# STM32_V2.net
KiCad netlist of a schematic drawn in EasyEDA Pro
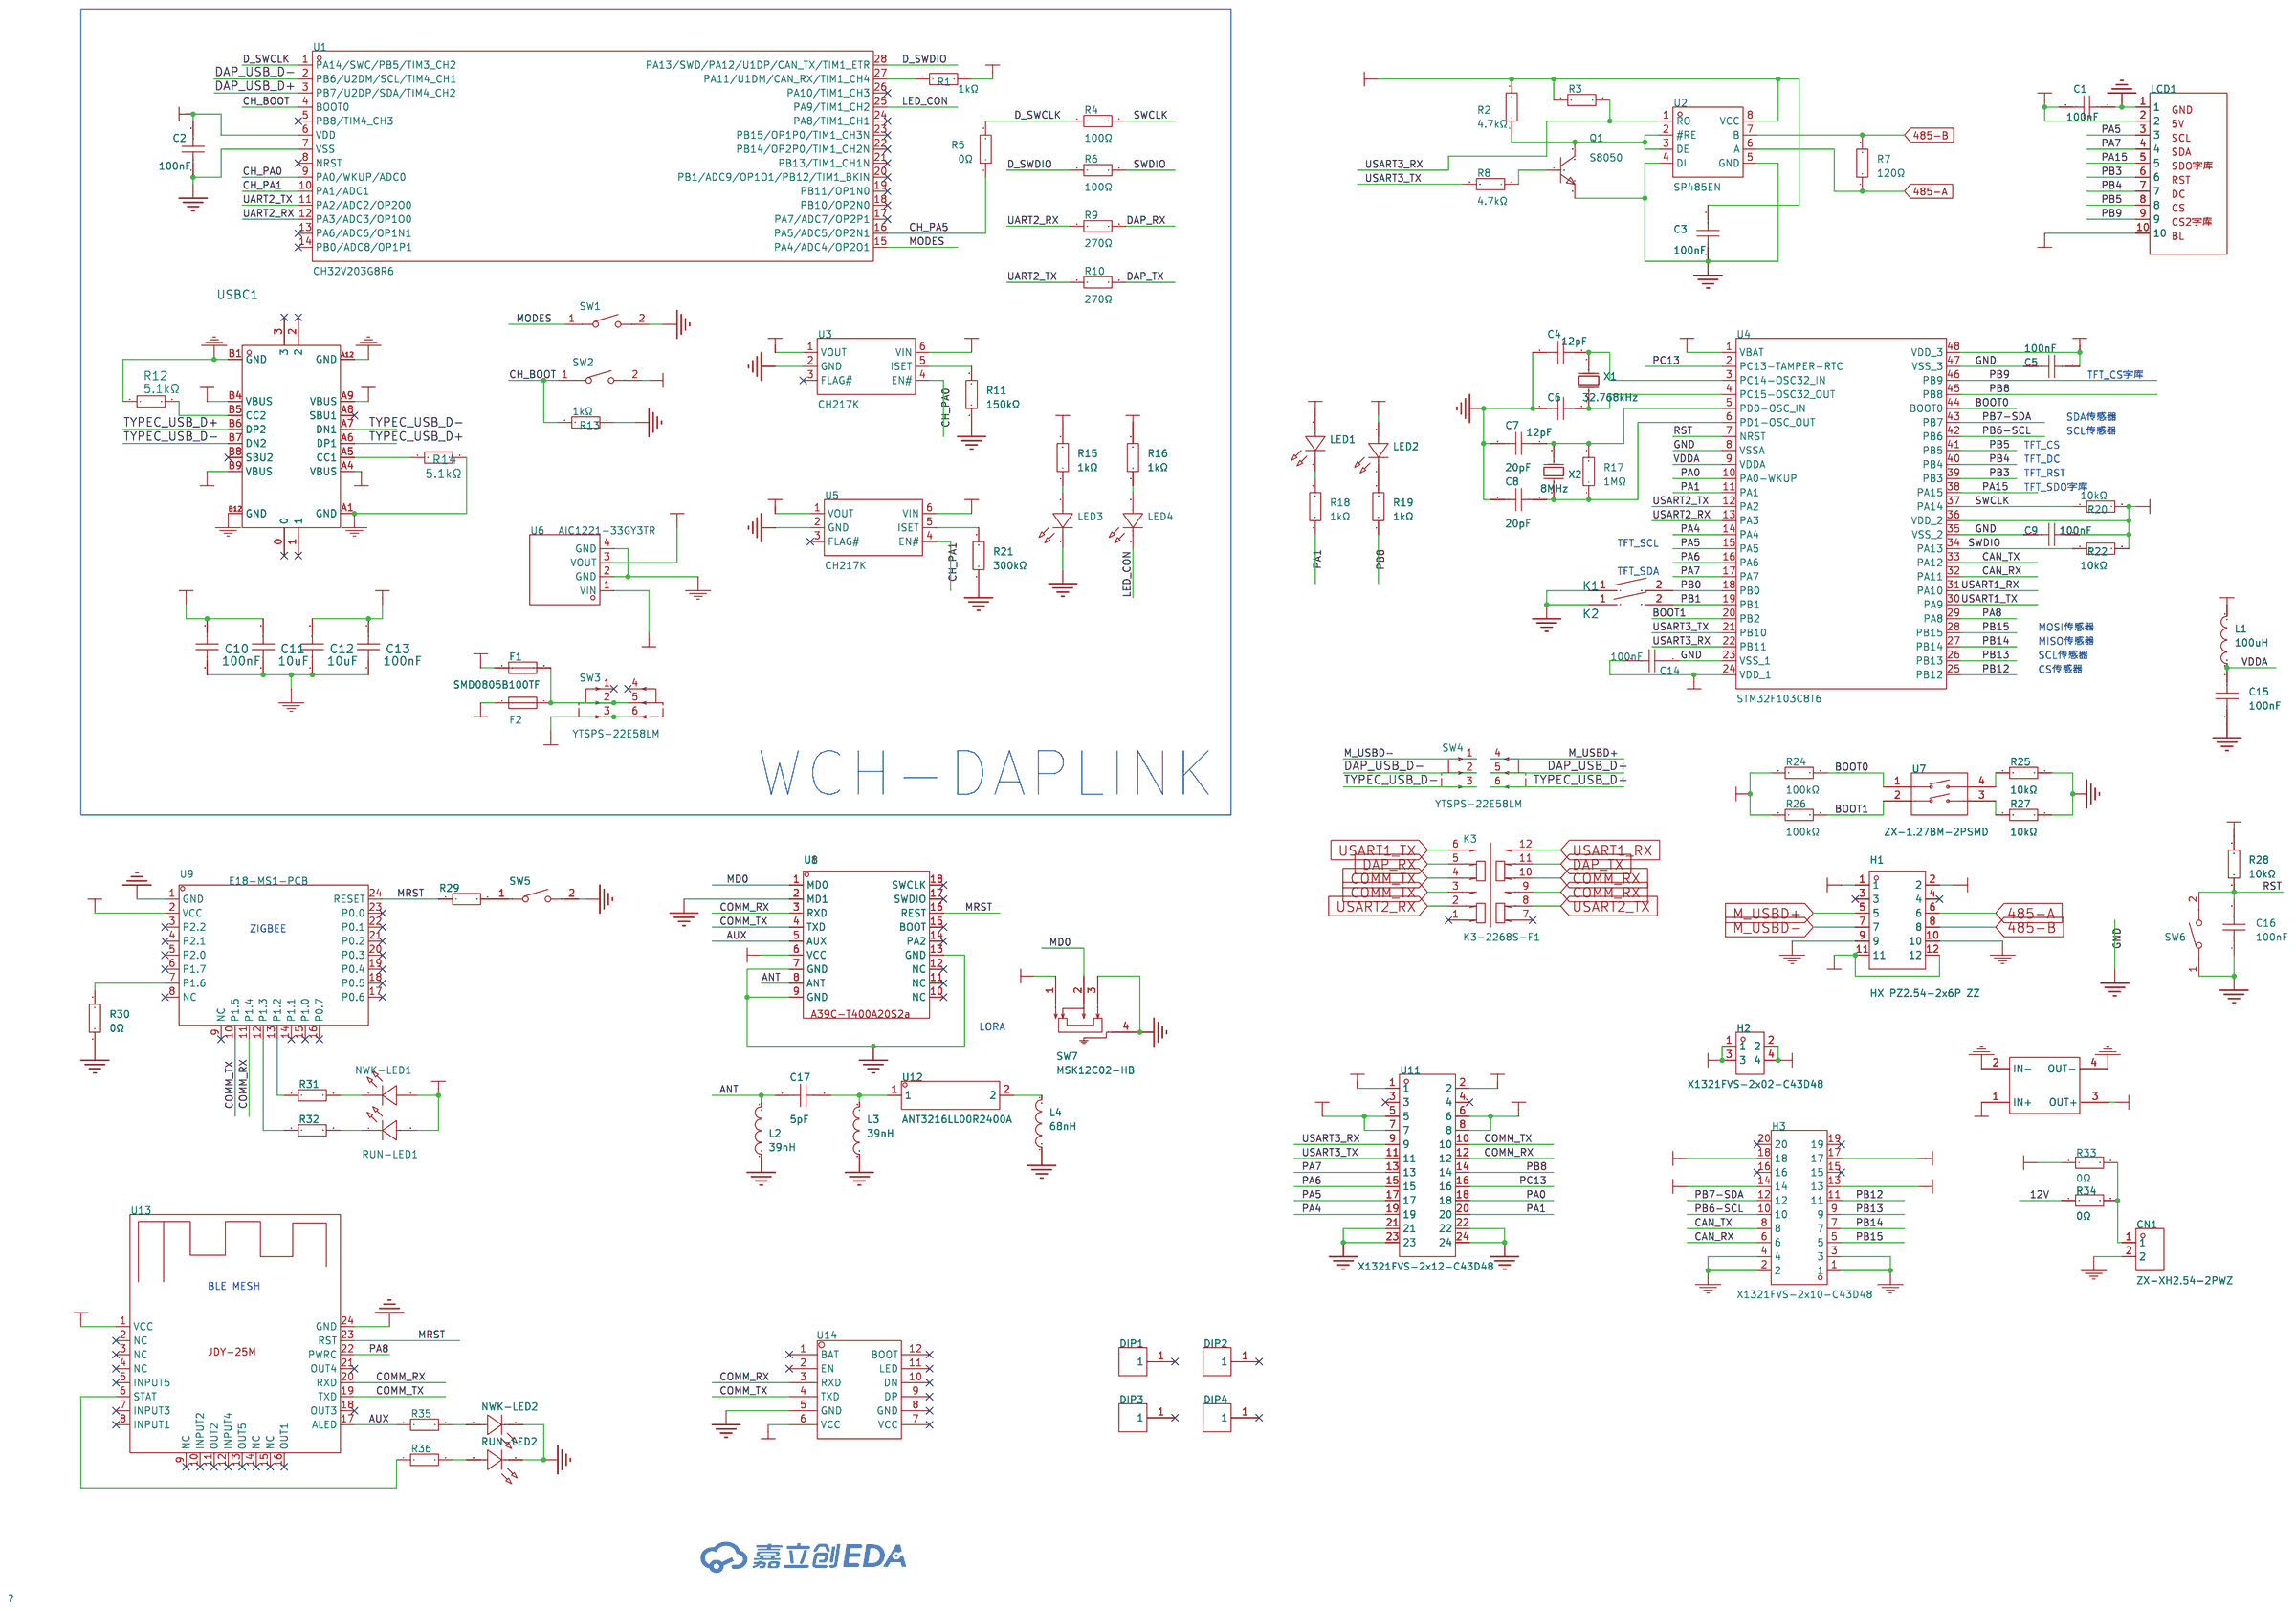
[diagram p0: schematic sheet]

(export (version "E")
  (design (tool "Eeschema 10.0.6"))
  (components
    (comp (ref "C1")
      (value "100nF")
      (footprint "easyedapro:C0603")
      (description "容值:100nF;精度:±10%;额定电压:50V;材质(温度系数):X7R;")
      (fields
        (field (name "Manufacturer Part") "CC0603KRX7R9BB104")
        (field (name "Manufacturer") "YAGEO(国巨)")
      )
      (libsource (lib "easyedapro") (part "CC0603KRX7R9BB104"))
    )
    (comp (ref "C2")
      (value "100nF")
      (footprint "easyedapro:C0603")
      (description "容值:100nF;精度:±10%;额定电压:50V;材质(温度系数):X7R;")
      (fields
        (field (name "Manufacturer Part") "CC0603KRX7R9BB104")
        (field (name "Manufacturer") "YAGEO(国巨)")
      )
      (libsource (lib "easyedapro") (part "CC0603KRX7R9BB104"))
    )
    (comp (ref "C3")
      (value "100nF")
      (footprint "easyedapro:C0603")
      (description "容值:100nF;精度:±10%;额定电压:50V;材质(温度系数):X7R;")
      (fields
        (field (name "Manufacturer Part") "CC0603KRX7R9BB104")
        (field (name "Manufacturer") "YAGEO(国巨)")
      )
      (libsource (lib "easyedapro") (part "CC0603KRX7R9BB104"))
    )
    (comp (ref "C4")
      (value "12pF")
      (footprint "easyedapro:C0603")
      (description "容值:12pF;精度:±1%;额定电压:50V;材质(温度系数):NP0;")
      (fields
        (field (name "Manufacturer Part") "CC0603FRNPO9BN120")
        (field (name "Manufacturer") "YAGEO(国巨)")
      )
      (libsource (lib "easyedapro") (part "CC0603FRNPO9BN120"))
    )
    (comp (ref "C5")
      (value "100nF")
      (footprint "easyedapro:C0603")
      (description "容值:100nF;精度:±10%;额定电压:50V;材质(温度系数):X7R;")
      (fields
        (field (name "Manufacturer Part") "CC0603KRX7R9BB104")
        (field (name "Manufacturer") "YAGEO(国巨)")
      )
      (libsource (lib "easyedapro") (part "CC0603KRX7R9BB104"))
    )
    (comp (ref "C6")
      (value "12pF")
      (footprint "easyedapro:C0603")
      (description "容值:12pF;精度:±1%;额定电压:50V;材质(温度系数):NP0;")
      (fields
        (field (name "Manufacturer Part") "CC0603FRNPO9BN120")
        (field (name "Manufacturer") "YAGEO(国巨)")
      )
      (libsource (lib "easyedapro") (part "CC0603FRNPO9BN120"))
    )
    (comp (ref "C7")
      (value "20pF")
      (footprint "easyedapro:C0603")
      (description "容值:20pF;精度:±1%;额定电压:50V;材质(温度系数):NP0;")
      (fields
        (field (name "Manufacturer Part") "CC0603FRNPO9BN200")
        (field (name "Manufacturer") "YAGEO(国巨)")
      )
      (libsource (lib "easyedapro") (part "CC0603FRNPO9BN200"))
    )
    (comp (ref "C8")
      (value "20pF")
      (footprint "easyedapro:C0603")
      (description "容值:20pF;精度:±1%;额定电压:50V;材质(温度系数):NP0;")
      (fields
        (field (name "Manufacturer Part") "CC0603FRNPO9BN200")
        (field (name "Manufacturer") "YAGEO(国巨)")
      )
      (libsource (lib "easyedapro") (part "CC0603FRNPO9BN200"))
    )
    (comp (ref "C9")
      (value "100nF")
      (footprint "easyedapro:C0603")
      (description "容值:100nF;精度:±10%;额定电压:50V;材质(温度系数):X7R;")
      (fields
        (field (name "Manufacturer Part") "CC0603KRX7R9BB104")
        (field (name "Manufacturer") "YAGEO(国巨)")
      )
      (libsource (lib "easyedapro") (part "CC0603KRX7R9BB104"))
    )
    (comp (ref "C10")
      (value "100nF")
      (fields
        (field (name "Manufacturer Part") "CC0603KRX7R9BB104")
        (field (name "Manufacturer") "YAGEO(国巨)")
      )
      (libsource (lib "easyedapro") (part "0.1u"))
    )
    (comp (ref "C11")
      (value "10uF")
      (fields
        (field (name "Manufacturer Part") "CL21A106KAYNNNE")
        (field (name "Manufacturer") "SAMSUNG(三星)")
      )
      (libsource (lib "easyedapro") (part "10u"))
    )
    (comp (ref "C12")
      (value "10uF")
      (fields
        (field (name "Manufacturer Part") "CL21A106KAYNNNE")
        (field (name "Manufacturer") "SAMSUNG(三星)")
      )
      (libsource (lib "easyedapro") (part "10u"))
    )
    (comp (ref "C13")
      (value "100nF")
      (fields
        (field (name "Manufacturer Part") "CC0603KRX7R9BB104")
        (field (name "Manufacturer") "YAGEO(国巨)")
      )
      (libsource (lib "easyedapro") (part "0.1u"))
    )
    (comp (ref "C14")
      (value "100nF")
      (footprint "easyedapro:C0603")
      (description "容值:100nF;精度:±10%;额定电压:50V;材质(温度系数):X7R;")
      (fields
        (field (name "Manufacturer Part") "CC0603KRX7R9BB104")
        (field (name "Manufacturer") "YAGEO(国巨)")
      )
      (libsource (lib "easyedapro") (part "CC0603KRX7R9BB104"))
    )
    (comp (ref "C15")
      (value "100nF")
      (footprint "easyedapro:C0603")
      (description "容值:100nF;精度:±10%;额定电压:50V;材质(温度系数):X7R;")
      (fields
        (field (name "Manufacturer Part") "CC0603KRX7R9BB104")
        (field (name "Manufacturer") "YAGEO(国巨)")
      )
      (libsource (lib "easyedapro") (part "CC0603KRX7R9BB104"))
    )
    (comp (ref "C16")
      (value "100nF")
      (footprint "easyedapro:C0603")
      (description "容值:100nF;精度:±10%;额定电压:50V;材质(温度系数):X7R;")
      (fields
        (field (name "Manufacturer Part") "CC0603KRX7R9BB104")
        (field (name "Manufacturer") "YAGEO(国巨)")
      )
      (libsource (lib "easyedapro") (part "CC0603KRX7R9BB104"))
    )
    (comp (ref "C17")
      (value "5pF")
      (footprint "easyedapro:C0603")
      (description "容值:5pF;额定电压:50V;材质(温度系数):NP0;")
      (fields
        (field (name "Manufacturer Part") "CC0603BRNPO9BN5R0")
        (field (name "Manufacturer") "YAGEO(国巨)")
      )
      (libsource (lib "easyedapro") (part "CC0603BRNPO9BN5R0"))
    )
    (comp (ref "CN1")
      (value "ZX-XH2.54-2PWZ")
      (footprint "easyedapro:CONN-TH_2P-P2.50_ZX-XH2.54-2PWZ")
      (fields (field (name "Manufacturer") "Megastar(兆星)"))
      (libsource (lib "easyedapro") (part "ZX-XH2.54-2PWZ"))
    )
    (comp (ref "DIP1")
      (value "~")
      (footprint "easyedapro:贴片铜柱M3*6+1")
      (libsource (lib "easyedapro") (part "贴片铜柱M3*6+1"))
    )
    (comp (ref "DIP2")
      (value "~")
      (footprint "easyedapro:贴片铜柱M3*6+1")
      (libsource (lib "easyedapro") (part "贴片铜柱M3*6+1"))
    )
    (comp (ref "DIP3")
      (value "~")
      (footprint "easyedapro:贴片铜柱M3*6+1")
      (libsource (lib "easyedapro") (part "贴片铜柱M3*6+1"))
    )
    (comp (ref "DIP4")
      (value "~")
      (footprint "easyedapro:贴片铜柱M3*6+1")
      (libsource (lib "easyedapro") (part "贴片铜柱M3*6+1"))
    )
    (comp (ref "F1")
      (value "SMD0805B100TF")
      (footprint "easyedapro:F0805")
      (description "最大电压:6V;最大电流:100A;保持电流:500mA;跳闸电流:1A;最大动作时间:100ms;")
      (fields (field (name "Manufacturer") "Brightking(台湾君耀)"))
      (libsource (lib "easyedapro") (part "SMD0805B050TF"))
    )
    (comp (ref "F2")
      (value "SMD0805B100TF")
      (footprint "easyedapro:F0805")
      (description "最大电压:6V;最大电流:100A;保持电流:500mA;跳闸电流:1A;最大动作时间:100ms;")
      (fields (field (name "Manufacturer") "Brightking(台湾君耀)"))
      (libsource (lib "easyedapro") (part "SMD0805B050TF"))
    )
    (comp (ref "H1")
      (value "HX PZ2.54-2x6P ZZ")
      (fields (field (name "Manufacturer") "hanxia(韩下)"))
      (libsource (lib "easyedapro") (part "PZ2.54-2X6-11.2"))
    )
    (comp (ref "H2")
      (value "X1321FVS-2x02-C43D48")
      (footprint "easyedapro:HDR-SMD_4P-P1.27-V-F-R2-C2-LS4.8")
      (fields (field (name "Manufacturer") "XKB Connectivity(中国星坤)"))
      (libsource (lib "easyedapro") (part "X1321FVS-2X02-C43D48"))
    )
    (comp (ref "H3")
      (value "X1321FVS-2x10-C43D48")
      (footprint "easyedapro:HDR-SMD_20P-P1.27-V-F-R2-C10-LS4.8")
      (fields (field (name "Manufacturer") "XKB Connectivity(中国星坤)"))
      (libsource (lib "easyedapro") (part "X1321FVS-2X10-C43D48"))
    )
    (comp (ref "K1")
      (value "TS665WS")
      (fields (field (name "Manufacturer") "SHOU HAN(首韩)"))
      (libsource (lib "easyedapro") (part "TSA343G00D-250J2"))
    )
    (comp (ref "K2")
      (value "TS665WS")
      (fields (field (name "Manufacturer") "SHOU HAN(首韩)"))
      (libsource (lib "easyedapro") (part "TSA343G00D-250J2"))
    )
    (comp (ref "K3")
      (value "5.1kΩ")
      (footprint "easyedapro:SW-TH_K3-2268S-F1")
      (description "额定电流(DC):300mA;额定电压(DC):6V;额定电流(AC):-;额定电压(AC):-;电路结构:四刀双掷;安装方式:卧贴;机械寿命:1万次;开关颜色:黑色;")
      (fields (field (name "Manufacturer Part") "K3-2268S-F1") (field (name "Manufacturer") "韩国韩荣"))
      (libsource (lib "easyedapro") (part "K3-2268S-F1"))
    )
    (comp (ref "L1")
      (value "100uH")
      (footprint "easyedapro:L0805")
      (description "电感值:100uH;精度:±10%;额定电流:2mA;饱和电流(Isat):-;直流电阻(DCR):2.5Ω;")
      (fields (field (name "Manufacturer Part") "MLF2012C101KT000") (field (name "Manufacturer") "TDK"))
      (libsource (lib "easyedapro") (part "MLF2012C101KT000"))
    )
    (comp (ref "L2")
      (value "39nH")
      (footprint "easyedapro:L0603")
      (description "电感值:39nH;精度:±5%;额定电流:300mA;饱和电流(Isat):-;直流电阻(DCR):700mΩ;")
      (fields
        (field (name "Manufacturer Part") "SDCL1608C39NJTDF")
        (field (name "Manufacturer") "Sunlord(顺络)")
      )
      (libsource (lib "easyedapro") (part "SDCL1608C39NJTDF"))
    )
    (comp (ref "L3")
      (value "39nH")
      (footprint "easyedapro:L0603")
      (description "电感值:39nH;精度:±5%;额定电流:300mA;饱和电流(Isat):-;直流电阻(DCR):700mΩ;")
      (fields
        (field (name "Manufacturer Part") "SDCL1608C39NJTDF")
        (field (name "Manufacturer") "Sunlord(顺络)")
      )
      (libsource (lib "easyedapro") (part "SDCL1608C39NJTDF"))
    )
    (comp (ref "L4")
      (value "68nH")
      (footprint "easyedapro:L0603")
      (description "电感值:68nH;精度:±5%;额定电流:300mA;饱和电流(Isat):-;直流电阻(DCR):850mΩ;")
      (fields
        (field (name "Manufacturer Part") "SDCL1608C68NJTDF")
        (field (name "Manufacturer") "Sunlord(顺络)")
      )
      (libsource (lib "easyedapro") (part "SDCL1608C68NJTF"))
    )
    (comp (ref "LCD1")
      (value "~")
      (footprint "easyedapro:1.54寸带字库液晶屏")
      (libsource (lib "easyedapro") (part "1.54寸带字库液晶屏"))
    )
    (comp (ref "LED1")
      (value "XL-1608UBC-04")
      (footprint "easyedapro:LED0603-RD_BLUE")
      (fields (field (name "Manufacturer") "XINGLIGHT(成兴光)"))
      (libsource (lib "easyedapro") (part "XL-1608UBC-04"))
    )
    (comp (ref "LED2")
      (value "XL-1608UBC-04")
      (footprint "easyedapro:LED0603-RD_BLUE")
      (fields (field (name "Manufacturer") "XINGLIGHT(成兴光)"))
      (libsource (lib "easyedapro") (part "XL-1608UBC-04"))
    )
    (comp (ref "LED3")
      (value "XL-1608UBC-04")
      (footprint "easyedapro:LED0603-RD_BLUE")
      (fields (field (name "Manufacturer") "XINGLIGHT(成兴光)"))
      (libsource (lib "easyedapro") (part "XL-1608UBC-04"))
    )
    (comp (ref "LED4")
      (value "XL-1608UBC-04")
      (footprint "easyedapro:LED0603-RD_BLUE")
      (fields (field (name "Manufacturer") "XINGLIGHT(成兴光)"))
      (libsource (lib "easyedapro") (part "XL-1608UBC-04"))
    )
    (comp (ref "NWK-LED1")
      (value "XL-1608UBC-04")
      (fields (field (name "Manufacturer") "XINGLIGHT(成兴光)"))
      (libsource (lib "") (part "XL-1608UBC-04_1"))
    )
    (comp (ref "NWK-LED2")
      (value "XL-1608UBC-04")
      (fields (field (name "Manufacturer") "XINGLIGHT(成兴光)"))
      (libsource (lib "") (part "XL-1608UBC-04_1"))
    )
    (comp (ref "Q1")
      (value "S8050")
      (footprint "easyedapro:SOT-23-3_L2.9-W1.3-P1.90-LS2.4-BR")
      (description "晶体管类型:NPN;集电极电流(Ic):500mA;集射极击穿电压(Vceo):25V;功率(Pd):300mW;直流电流增益(hFE@Ic,Vce):400@50mA,1V;")
      (fields (field (name "Manufacturer") "YONGYUTAI(永裕泰)"))
      (libsource (lib "easyedapro") (part "S8050_C2891804"))
    )
    (comp (ref "R1")
      (value "1kΩ")
      (footprint "easyedapro:R0603")
      (description "电阻类型:厚膜电阻;阻值:1kΩ;精度:±1%;功率:100mW;最大工作电压:75V;温度系数:±100ppm/°C;")
      (fields
        (field (name "Manufacturer Part") "0603WAF1001T5E")
        (field (name "Manufacturer") "UNI-ROYAL(厚声)")
      )
      (libsource (lib "easyedapro") (part "0603WAF1001T5E"))
    )
    (comp (ref "R2")
      (value "4.7kΩ")
      (footprint "easyedapro:R0603")
      (description "电阻类型:厚膜电阻;阻值:4.7kΩ;精度:±1%;功率:100mW;最大工作电压:75V;温度系数:±100ppm/°C;")
      (fields
        (field (name "Manufacturer Part") "0603WAF4701T5E")
        (field (name "Manufacturer") "UNI-ROYAL(厚声)")
      )
      (libsource (lib "easyedapro") (part "0603WAF4701T5E"))
    )
    (comp (ref "R3")
      (value "4.7kΩ")
      (footprint "easyedapro:R0603")
      (description "电阻类型:厚膜电阻;阻值:4.7kΩ;精度:±1%;功率:100mW;最大工作电压:75V;温度系数:±100ppm/°C;")
      (fields
        (field (name "Manufacturer Part") "0603WAF4701T5E")
        (field (name "Manufacturer") "UNI-ROYAL(厚声)")
      )
      (libsource (lib "easyedapro") (part "0603WAF4701T5E"))
    )
    (comp (ref "R4")
      (value "100Ω")
      (footprint "easyedapro:R0603")
      (description "电阻类型:厚膜电阻;阻值:100Ω;精度:±1%;功率:100mW;最大工作电压:75V;温度系数:±200ppm/°C;")
      (fields
        (field (name "Manufacturer Part") "0603WAF1000T5E")
        (field (name "Manufacturer") "UNI-ROYAL(厚声)")
      )
      (libsource (lib "easyedapro") (part "0603WAF1000T5E"))
    )
    (comp (ref "R5")
      (value "0Ω")
      (footprint "easyedapro:R0603")
      (description "电阻类型:厚膜电阻;阻值:0Ω;精度:±1%;功率:100mW;最大工作电压:75V;")
      (fields
        (field (name "Manufacturer Part") "0603WAF0000T5E")
        (field (name "Manufacturer") "UNI-ROYAL(厚声)")
      )
      (libsource (lib "easyedapro") (part "0603WAF0000T5E"))
    )
    (comp (ref "R6")
      (value "100Ω")
      (footprint "easyedapro:R0603")
      (description "电阻类型:厚膜电阻;阻值:100Ω;精度:±1%;功率:100mW;最大工作电压:75V;温度系数:±200ppm/°C;")
      (fields
        (field (name "Manufacturer Part") "0603WAF1000T5E")
        (field (name "Manufacturer") "UNI-ROYAL(厚声)")
      )
      (libsource (lib "easyedapro") (part "0603WAF1000T5E"))
    )
    (comp (ref "R7")
      (value "120Ω")
      (footprint "easyedapro:R1206")
      (description "电阻类型:厚膜电阻;阻值:120Ω;精度:±5%;功率:250mW;最大工作电压:200V;温度系数:±100ppm/°C;")
      (fields
        (field (name "Manufacturer Part") "1206W4J0121T5E")
        (field (name "Manufacturer") "UNI-ROYAL(厚声)")
      )
      (libsource (lib "easyedapro") (part "1206W4J0121T5E"))
    )
    (comp (ref "R8")
      (value "4.7kΩ")
      (footprint "easyedapro:R0603")
      (description "电阻类型:厚膜电阻;阻值:4.7kΩ;精度:±1%;功率:100mW;最大工作电压:75V;温度系数:±100ppm/°C;")
      (fields
        (field (name "Manufacturer Part") "0603WAF4701T5E")
        (field (name "Manufacturer") "UNI-ROYAL(厚声)")
      )
      (libsource (lib "easyedapro") (part "0603WAF4701T5E"))
    )
    (comp (ref "R9")
      (value "270Ω")
      (footprint "easyedapro:R0603")
      (description "电阻类型:厚膜电阻;阻值:270Ω;精度:±1%;功率:100mW;最大工作电压:75V;温度系数:±100ppm/°C;")
      (fields
        (field (name "Manufacturer Part") "0603WAF2700T5E")
        (field (name "Manufacturer") "UNI-ROYAL(厚声)")
      )
      (libsource (lib "easyedapro") (part "0603WAF2700T5E"))
    )
    (comp (ref "R10")
      (value "270Ω")
      (footprint "easyedapro:R0603")
      (description "电阻类型:厚膜电阻;阻值:270Ω;精度:±1%;功率:100mW;最大工作电压:75V;温度系数:±100ppm/°C;")
      (fields
        (field (name "Manufacturer Part") "0603WAF2700T5E")
        (field (name "Manufacturer") "UNI-ROYAL(厚声)")
      )
      (libsource (lib "easyedapro") (part "0603WAF2700T5E"))
    )
    (comp (ref "R11")
      (value "150kΩ")
      (footprint "easyedapro:R0603")
      (description "电阻类型:厚膜电阻;阻值:150kΩ;精度:±1%;功率:100mW;最大工作电压:75V;温度系数:±100ppm/°C;")
      (fields
        (field (name "Manufacturer Part") "0603WAF1503T5E")
        (field (name "Manufacturer") "UNI-ROYAL(厚声)")
      )
      (libsource (lib "easyedapro") (part "0603WAF1503T5E"))
    )
    (comp (ref "R12") (value "5.1kΩ") (libsource (lib "easyedapro") (part "5.1K")))
    (comp (ref "R13")
      (value "1kΩ")
      (footprint "easyedapro:R0603")
      (description "电阻类型:厚膜电阻;阻值:1kΩ;精度:±1%;功率:100mW;最大工作电压:75V;温度系数:±100ppm/°C;")
      (fields
        (field (name "Manufacturer Part") "0603WAF1001T5E")
        (field (name "Manufacturer") "UNI-ROYAL(厚声)")
      )
      (libsource (lib "easyedapro") (part "0603WAF1001T5E"))
    )
    (comp (ref "R14") (value "5.1kΩ") (libsource (lib "easyedapro") (part "5.1K")))
    (comp (ref "R15")
      (value "1kΩ")
      (footprint "easyedapro:R0603")
      (description "电阻类型:厚膜电阻;阻值:1kΩ;精度:±1%;功率:100mW;最大工作电压:75V;温度系数:±100ppm/°C;")
      (fields
        (field (name "Manufacturer Part") "0603WAF1001T5E")
        (field (name "Manufacturer") "UNI-ROYAL(厚声)")
      )
      (libsource (lib "easyedapro") (part "0603WAF1001T5E"))
    )
    (comp (ref "R16")
      (value "1kΩ")
      (footprint "easyedapro:R0603")
      (description "电阻类型:厚膜电阻;阻值:1kΩ;精度:±1%;功率:100mW;最大工作电压:75V;温度系数:±100ppm/°C;")
      (fields
        (field (name "Manufacturer Part") "0603WAF1001T5E")
        (field (name "Manufacturer") "UNI-ROYAL(厚声)")
      )
      (libsource (lib "easyedapro") (part "0603WAF1001T5E"))
    )
    (comp (ref "R17")
      (value "1MΩ")
      (footprint "easyedapro:R0603")
      (description "电阻类型:厚膜电阻;阻值:1MΩ;精度:±1%;功率:100mW;最大工作电压:75V;温度系数:±100ppm/°C;")
      (fields
        (field (name "Manufacturer Part") "0603WAF1004T5E")
        (field (name "Manufacturer") "UNI-ROYAL(厚声)")
      )
      (libsource (lib "easyedapro") (part "0603WAF1004T5E"))
    )
    (comp (ref "R18")
      (value "1kΩ")
      (footprint "easyedapro:R0603")
      (description "电阻类型:厚膜电阻;阻值:1kΩ;精度:±1%;功率:100mW;最大工作电压:75V;温度系数:±100ppm/°C;")
      (fields
        (field (name "Manufacturer Part") "0603WAF1001T5E")
        (field (name "Manufacturer") "UNI-ROYAL(厚声)")
      )
      (libsource (lib "easyedapro") (part "0603WAF1001T5E"))
    )
    (comp (ref "R19")
      (value "1kΩ")
      (footprint "easyedapro:R0603")
      (description "电阻类型:厚膜电阻;阻值:1kΩ;精度:±1%;功率:100mW;最大工作电压:75V;温度系数:±100ppm/°C;")
      (fields
        (field (name "Manufacturer Part") "0603WAF1001T5E")
        (field (name "Manufacturer") "UNI-ROYAL(厚声)")
      )
      (libsource (lib "easyedapro") (part "0603WAF1001T5E"))
    )
    (comp (ref "R20")
      (value "10kΩ")
      (footprint "easyedapro:R0603")
      (description "电阻类型:厚膜电阻;阻值:10kΩ;精度:±1%;功率:100mW;最大工作电压:75V;温度系数:±100ppm/°C;")
      (fields
        (field (name "Manufacturer Part") "0603WAF1002T5E")
        (field (name "Manufacturer") "UNI-ROYAL(厚声)")
      )
      (libsource (lib "easyedapro") (part "0603WAF1002T5E"))
    )
    (comp (ref "R21")
      (value "300kΩ")
      (footprint "easyedapro:R0603")
      (description "电阻类型:厚膜电阻;阻值:300kΩ;精度:±1%;功率:100mW;最大工作电压:75V;温度系数:±100ppm/°C;")
      (fields
        (field (name "Manufacturer Part") "0603WAF3003T5E")
        (field (name "Manufacturer") "UNI-ROYAL(厚声)")
      )
      (libsource (lib "easyedapro") (part "0603WAF3003T5E"))
    )
    (comp (ref "R22")
      (value "10kΩ")
      (footprint "easyedapro:R0603")
      (description "电阻类型:厚膜电阻;阻值:10kΩ;精度:±1%;功率:100mW;最大工作电压:75V;温度系数:±100ppm/°C;")
      (fields
        (field (name "Manufacturer Part") "0603WAF1002T5E")
        (field (name "Manufacturer") "UNI-ROYAL(厚声)")
      )
      (libsource (lib "easyedapro") (part "0603WAF1002T5E"))
    )
    (comp (ref "R24")
      (value "100kΩ")
      (footprint "easyedapro:R0603")
      (description "电阻类型:厚膜电阻;阻值:100kΩ;精度:±1%;功率:100mW;最大工作电压:75V;温度系数:±100ppm/°C;")
      (fields
        (field (name "Manufacturer Part") "0603WAF1003T5E")
        (field (name "Manufacturer") "UNI-ROYAL(厚声)")
      )
      (libsource (lib "easyedapro") (part "0603WAF1003T5E"))
    )
    (comp (ref "R25")
      (value "10kΩ")
      (footprint "easyedapro:R0603")
      (description "电阻类型:厚膜电阻;阻值:10kΩ;精度:±1%;功率:100mW;最大工作电压:75V;温度系数:±100ppm/°C;")
      (fields
        (field (name "Manufacturer Part") "0603WAF1002T5E")
        (field (name "Manufacturer") "UNI-ROYAL(厚声)")
      )
      (libsource (lib "easyedapro") (part "0603WAF1002T5E"))
    )
    (comp (ref "R26")
      (value "100kΩ")
      (footprint "easyedapro:R0603")
      (description "电阻类型:厚膜电阻;阻值:100kΩ;精度:±1%;功率:100mW;最大工作电压:75V;温度系数:±100ppm/°C;")
      (fields
        (field (name "Manufacturer Part") "0603WAF1003T5E")
        (field (name "Manufacturer") "UNI-ROYAL(厚声)")
      )
      (libsource (lib "easyedapro") (part "0603WAF1003T5E"))
    )
    (comp (ref "R27")
      (value "10kΩ")
      (footprint "easyedapro:R0603")
      (description "电阻类型:厚膜电阻;阻值:10kΩ;精度:±1%;功率:100mW;最大工作电压:75V;温度系数:±100ppm/°C;")
      (fields
        (field (name "Manufacturer Part") "0603WAF1002T5E")
        (field (name "Manufacturer") "UNI-ROYAL(厚声)")
      )
      (libsource (lib "easyedapro") (part "0603WAF1002T5E"))
    )
    (comp (ref "R28")
      (value "10kΩ")
      (footprint "easyedapro:R0603")
      (description "电阻类型:厚膜电阻;阻值:10kΩ;精度:±1%;功率:100mW;最大工作电压:75V;温度系数:±100ppm/°C;")
      (fields
        (field (name "Manufacturer Part") "0603WAF1002T5E")
        (field (name "Manufacturer") "UNI-ROYAL(厚声)")
      )
      (libsource (lib "easyedapro") (part "0603WAF1002T5E"))
    )
    (comp (ref "R29")
      (value "10kΩ")
      (fields
        (field (name "Manufacturer Part") "0603WAF1002T5E")
        (field (name "Manufacturer") "UNI-ROYAL(厚声)")
      )
      (libsource (lib "easyedapro") (part "0603WAF1002T5E"))
    )
    (comp (ref "R30")
      (value "0Ω")
      (fields
        (field (name "Manufacturer Part") "0603WAF0000T5E")
        (field (name "Manufacturer") "UNI-ROYAL(厚声)")
      )
      (libsource (lib "easyedapro") (part "0603WAF0000T5E"))
    )
    (comp (ref "R31")
      (value "1kΩ")
      (fields
        (field (name "Manufacturer Part") "0603WAF1001T5E")
        (field (name "Manufacturer") "UNI-ROYAL(厚声)")
      )
      (libsource (lib "easyedapro") (part "0603WAF1001T5E"))
    )
    (comp (ref "R32")
      (value "1kΩ")
      (fields
        (field (name "Manufacturer Part") "0603WAF1001T5E")
        (field (name "Manufacturer") "UNI-ROYAL(厚声)")
      )
      (libsource (lib "easyedapro") (part "0603WAF1001T5E"))
    )
    (comp (ref "R33")
      (value "0Ω")
      (footprint "easyedapro:R0603")
      (description "电阻类型:厚膜电阻;阻值:0Ω;精度:±1%;功率:100mW;最大工作电压:75V;")
      (fields
        (field (name "Manufacturer Part") "0603WAF0000T5E")
        (field (name "Manufacturer") "UNI-ROYAL(厚声)")
      )
      (libsource (lib "easyedapro") (part "0603WAF0000T5E"))
    )
    (comp (ref "R34")
      (value "0Ω")
      (footprint "easyedapro:R0603")
      (description "电阻类型:厚膜电阻;阻值:0Ω;精度:±1%;功率:100mW;最大工作电压:75V;")
      (fields
        (field (name "Manufacturer Part") "0603WAF0000T5E")
        (field (name "Manufacturer") "UNI-ROYAL(厚声)")
      )
      (libsource (lib "easyedapro") (part "0603WAF0000T5E"))
    )
    (comp (ref "R35")
      (value "1kΩ")
      (fields
        (field (name "Manufacturer Part") "0603WAF1001T5E")
        (field (name "Manufacturer") "UNI-ROYAL(厚声)")
      )
      (libsource (lib "easyedapro") (part "0603WAF1001T5E"))
    )
    (comp (ref "R36")
      (value "1kΩ")
      (fields
        (field (name "Manufacturer Part") "0603WAF1001T5E")
        (field (name "Manufacturer") "UNI-ROYAL(厚声)")
      )
      (libsource (lib "easyedapro") (part "0603WAF1001T5E"))
    )
    (comp (ref "RUN-LED1")
      (value "XL-1608UBC-04")
      (fields (field (name "Manufacturer") "XINGLIGHT(成兴光)"))
      (libsource (lib "") (part "XL-1608UBC-04_1"))
    )
    (comp (ref "RUN-LED2")
      (value "XL-1608UBC-04")
      (fields (field (name "Manufacturer") "XINGLIGHT(成兴光)"))
      (libsource (lib "") (part "XL-1608UBC-04_1"))
    )
    (comp (ref "SW1")
      (value "TS-1088-AR02016")
      (footprint "easyedapro:SW-SMD_L3.9-W3.0-P4.45")
      (fields (field (name "Manufacturer") "XUNPU(讯普)"))
      (libsource (lib "easyedapro") (part "TS-1088-AR02016"))
    )
    (comp (ref "SW2")
      (value "TS-1088-AR02016")
      (footprint "easyedapro:SW-SMD_L3.9-W3.0-P4.45")
      (fields (field (name "Manufacturer") "XUNPU(讯普)"))
      (libsource (lib "easyedapro") (part "TS-1088-AR02016"))
    )
    (comp (ref "SW3")
      (value "YTSPS-22E58LM")
      (footprint "easyedapro:SW-SMD_6P-L5.8-W5.8-P2.00-LS8.0_YTSPS-22E58LM")
      (description "电路结构:双刀双掷;自锁/无锁:自锁;安装方式:立贴;触点电流:500mA;额定电压 (DC):50V;作用力:1.8N;机械寿命:2万次;")
      (fields (field (name "Manufacturer") "YIYUAN(怡远)"))
      (libsource (lib "easyedapro") (part "YTSPS-22E58LM"))
    )
    (comp (ref "SW4")
      (value "YTSPS-22E58LM")
      (footprint "easyedapro:SW-SMD_6P-L5.8-W5.8-P2.00-LS8.0_YTSPS-22E58LM")
      (description "电路结构:双刀双掷;自锁/无锁:自锁;安装方式:立贴;触点电流:500mA;额定电压 (DC):50V;作用力:1.8N;机械寿命:2万次;")
      (fields (field (name "Manufacturer") "YIYUAN(怡远)"))
      (libsource (lib "easyedapro") (part "YTSPS-22E58LM"))
    )
    (comp (ref "SW5")
      (value "TS-1088-AR02016")
      (footprint "easyedapro:SW-SMD_L3.9-W3.0-P4.45")
      (fields (field (name "Manufacturer") "XUNPU(讯普)"))
      (libsource (lib "easyedapro") (part "TS-1088-AR02016"))
    )
    (comp (ref "SW6")
      (value "TS-1088-AR02016")
      (footprint "easyedapro:SW-SMD_L3.9-W3.0-P4.45")
      (fields (field (name "Manufacturer") "XUNPU(讯普)"))
      (libsource (lib "easyedapro") (part "TS-1088-AR02016"))
    )
    (comp (ref "SW7")
      (value "MSK12C02-HB")
      (footprint "easyedapro:SW-TH_MSK12C02-HB-1")
      (fields (field (name "Manufacturer") "SHOU HAN(首韩)"))
      (libsource (lib "easyedapro") (part "MSK12C02-HB"))
    )
    (comp (ref "U1")
      (value "CH32V203G8R6")
      (footprint "easyedapro:QSOP-28_L9.9-W3.9-P0.64-LS6.0-BL")
      (fields (field (name "Manufacturer") "WCH(南京沁恒)"))
      (libsource (lib "easyedapro") (part "CH32V203G8R6"))
    )
    (comp (ref "U2")
      (value "SP485EN")
      (footprint "easyedapro:SOP-8_L5.0-W4.0-P1.27-LS6.0-BL")
      (description "类型:收发器;数据速率:2.5Mbps;驱动器/接收器:1/1;")
      (fields (field (name "Manufacturer") "UMW(友台半导体)"))
      (libsource (lib "easyedapro") (part "SP485EN"))
    )
    (comp (ref "U3")
      (value "CH217K")
      (footprint "easyedapro:SOT-23-6_L2.9-W1.6-P0.95-LS2.8-BL")
      (description "类型:负载开关;通道数:1;输入控制逻辑:低电平有效;输出电流:2.7A;工作电压:2.7V~5.5V;导通电阻:70mΩ;")
      (fields (field (name "Manufacturer") "WCH(南京沁恒)"))
      (libsource (lib "easyedapro") (part "CH217K"))
    )
    (comp (ref "U4")
      (value "STM32F103C8T6")
      (footprint "easyedapro:LQFP-48_L7.0-W7.0-P0.50-LS9.0-BL")
      (description "CPU内核:ARM-M3;CPU最大主频:72MHz;应用领域:-;")
      (fields (field (name "Manufacturer") "ST(意法半导体)"))
      (libsource (lib "easyedapro") (part "STM32F103C8T6"))
    )
    (comp (ref "U5")
      (value "CH217K")
      (footprint "easyedapro:SOT-23-6_L2.9-W1.6-P0.95-LS2.8-BL")
      (description "类型:负载开关;通道数:1;输入控制逻辑:低电平有效;输出电流:2.7A;工作电压:2.7V~5.5V;导通电阻:70mΩ;")
      (fields (field (name "Manufacturer") "WCH(南京沁恒)"))
      (libsource (lib "easyedapro") (part "CH217K"))
    )
    (comp (ref "U6")
      (value "AIC1221-33GY3TR")
      (footprint "easyedapro:SOT-223_L6.5-W3.5-P2.30-LS7.0-BR")
      (description "输出类型:固定;输出极性:正;最大输入电压:6V;输出电压:3.3V;输出电流:2A;电源纹波抑制比(PSRR):70dB@(1kHz);")
      (fields (field (name "Manufacturer") "AIC(沛亨半导体)"))
      (libsource (lib "easyedapro") (part "AIC1221-33GY3TR"))
    )
    (comp (ref "U7")
      (value "ZX-1.27BM-2PSMD")
      (footprint "easyedapro:SW-SMD_2P-L5.4-W4.1-P1.27-LS8.4")
      (description "类型:平拨,凹槽式;电路结构:单刀单掷;开关位数:2位;额定电流:25mA;额定电压:24V;使用寿命:3千次;颜色:黑色;")
      (fields (field (name "Manufacturer") "Megastar(兆星)"))
      (libsource (lib "easyedapro") (part "ZX-1.27BM-2PSMD"))
    )
    (comp (ref "U8")
      (value "~")
      (footprint "easyedapro:Lora小模块")
      (libsource (lib "easyedapro") (part "lora小模块"))
    )
    (comp (ref "U9")
      (value "E18-MS1-PCB")
      (footprint "easyedapro:WIRELM-SMD_E18-MS1-PCB")
      (description "发射功率:4dBm;核心芯片:CC2530;支持接口:-;传输距离:200m;接收灵敏度:-97dBm;")
      (fields (field (name "Manufacturer") "EBYTE(亿佰特)"))
      (libsource (lib "easyedapro") (part "E18-MS1-PCB"))
    )
    (comp (ref "U10")
      (value "~")
      (footprint "easyedapro:DC-DCmini")
      (libsource (lib "easyedapro") (part "DC-DC模块mini"))
    )
    (comp (ref "U11")
      (value "X1321FVS-2x12-C43D48")
      (footprint "easyedapro:HDR-SMD_24P-P1.27-V-F-R2-C12-LS4.8")
      (fields (field (name "Manufacturer") "XKB Connectivity(中国星坤)"))
      (libsource (lib "easyedapro") (part "X1321FVS-2X12-C43D48"))
    )
    (comp (ref "U12")
      (value "ANT3216LL00R2400A")
      (footprint "easyedapro:ANT-SMD_L3.2-W1.6")
      (description "天线类型:芯片天线;中心频点:2.45GHz;带宽:160MHz;峰值增益:5.05dBi;极化方式:线性;功率容量:1W;驻波比:-;")
      (fields (field (name "Manufacturer") "YAGEO(国巨)"))
      (libsource (lib "easyedapro") (part "ANT3216LL00R2400A"))
    )
    (comp (ref "U13")
      (value "~")
      (footprint "easyedapro:JDY-25M蓝牙模块")
      (libsource (lib "easyedapro") (part "JDY-25M蓝牙模块"))
    )
    (comp (ref "U14")
      (value "~")
      (footprint "easyedapro:度云4G模块")
      (libsource (lib "easyedapro") (part "度云4G模块"))
    )
    (comp (ref "USBC1") (value "TYPE-C-31-M-12") (libsource (lib "easyedapro") (part "type-c-31-m-12")))
    (comp (ref "X1")
      (value "32.768kHz")
      (footprint "easyedapro:CRYSTAL-SMD_L3.2-W1.5-1")
      (description "晶振类型:贴片晶振;频率:32.768kHz;常温频差:±20ppm;负载电容:12.5pF;频率稳定度:±30ppm;")
      (fields
        (field (name "Manufacturer Part") "XKXGI-SUA-32.768K")
        (field (name "Manufacturer") "YXC(扬兴晶振)")
      )
      (libsource (lib "easyedapro") (part "XKXGI-SUA-32.768K"))
    )
    (comp (ref "X2")
      (value "8MHz")
      (footprint "easyedapro:CRYSTAL-SMD_L5.0-W3.2")
      (description "晶振类型:贴片晶振;频率:8MHz;常温频差:±10ppm;负载电容:20pF;频率稳定度:±20ppm;")
      (fields
        (field (name "Manufacturer Part") "XG1EL89CSI-111YLC-8M")
        (field (name "Manufacturer") "YXC(扬兴晶振)")
      )
      (libsource (lib "easyedapro") (part "XG1EL89CSI-111YLC-8M"))
    )
  )
  (nets
    (net (code "1") (name "/ANT") (class "Default")
      (node (ref "C17") (pin "1") (pinfunction "1_1") (pintype "unspecified"))
      (node (ref "L2") (pin "2") (pinfunction "2_2") (pintype "unspecified"))
      (node (ref "U8") (pin "8") (pinfunction "ANT_8") (pintype "input"))
    )
    (net (code "2") (name "/AUX") (class "Default")
      (node (ref "R35") (pin "1") (pinfunction "1_1") (pintype "input"))
      (node (ref "U13") (pin "17") (pinfunction "ALED_17") (pintype "unspecified"))
      (node (ref "U8") (pin "5") (pinfunction "AUX_5") (pintype "input"))
    )
    (net (code "3") (name "/BOOT0") (class "Default")
      (node (ref "R24") (pin "2") (pinfunction "2_2") (pintype "input"))
      (node (ref "U4") (pin "44") (pinfunction "BOOT0_44") (pintype "unspecified"))
      (node (ref "U7") (pin "1") (pinfunction "1_1") (pintype "unspecified"))
    )
    (net (code "4") (name "/BOOT1") (class "Default")
      (node (ref "R26") (pin "2") (pinfunction "2_2") (pintype "input"))
      (node (ref "U4") (pin "20") (pinfunction "PB2_20") (pintype "unspecified"))
      (node (ref "U7") (pin "2") (pinfunction "2_2") (pintype "unspecified"))
    )
    (net (code "5") (name "/CAN_RX") (class "Default")
      (node (ref "H3") (pin "6") (pinfunction "6_6") (pintype "unspecified"))
      (node (ref "U4") (pin "32") (pinfunction "PA11_32") (pintype "unspecified"))
    )
    (net (code "6") (name "/CAN_TX") (class "Default")
      (node (ref "H3") (pin "8") (pinfunction "8_8") (pintype "unspecified"))
      (node (ref "U4") (pin "33") (pinfunction "PA12_33") (pintype "unspecified"))
    )
    (net (code "7") (name "/CH_BOOT") (class "Default")
      (node (ref "R13") (pin "2") (pinfunction "2_2") (pintype "input"))
      (node (ref "SW2") (pin "1") (pinfunction "1_1") (pintype "unspecified"))
      (node (ref "U1") (pin "4") (pinfunction "BOOT0_4") (pintype "unspecified"))
    )
    (net (code "8") (name "/CH_PA0") (class "Default")
      (node (ref "U1") (pin "9") (pinfunction "PA0/WKUP/ADC0_9") (pintype "unspecified"))
      (node (ref "U3") (pin "4") (pinfunction "EN#_4") (pintype "unspecified"))
    )
    (net (code "9") (name "/CH_PA1") (class "Default")
      (node (ref "U1") (pin "10") (pinfunction "PA1/ADC1_10") (pintype "unspecified"))
      (node (ref "U5") (pin "4") (pinfunction "EN#_4") (pintype "unspecified"))
    )
    (net (code "10") (name "/CH_PA5") (class "Default")
      (node (ref "R5") (pin "1") (pinfunction "1_1") (pintype "input"))
      (node (ref "U1") (pin "16") (pinfunction "PA5/ADC5/OP2N1_16") (pintype "unspecified"))
    )
    (net (code "11") (name "/DAP_USB_D+") (class "Default")
      (node (ref "SW4") (pin "5") (pinfunction "5_5") (pintype "unspecified"))
      (node (ref "U1") (pin "3") (pinfunction "PB7/U2DP/SDA/TIM4_CH2_3") (pintype "unspecified"))
    )
    (net (code "12") (name "/DAP_USB_D-") (class "Default")
      (node (ref "SW4") (pin "2") (pinfunction "2_2") (pintype "unspecified"))
      (node (ref "U1") (pin "2") (pinfunction "PB6/U2DM/SCL/TIM4_CH1_2") (pintype "unspecified"))
    )
    (net (code "13") (name "/D_SWCLK") (class "Default")
      (node (ref "R4") (pin "1") (pinfunction "1_1") (pintype "input"))
      (node (ref "R5") (pin "2") (pinfunction "2_2") (pintype "input"))
      (node (ref "U1") (pin "1") (pinfunction "PA14/SWC/PB5/TIM3_CH2_1") (pintype "unspecified"))
    )
    (net (code "14") (name "/D_SWDIO") (class "Default")
      (node (ref "R6") (pin "1") (pinfunction "1_1") (pintype "input"))
      (node (ref "U1") (pin "28") (pinfunction "PA13/SWD/PA12/U1DP/CAN_TX/TIM1_ETR_28") (pintype "unspecified"))
    )
    (net (code "15") (name "/LED_CON") (class "Default")
      (node (ref "LED4") (pin "1") (pinfunction "K_1") (pintype "unspecified"))
      (node (ref "U1") (pin "25") (pinfunction "PA9/TIM1_CH2_25") (pintype "unspecified"))
    )
    (net (code "16") (name "/MD0") (class "Default")
      (node (ref "SW7") (pin "2") (pinfunction "2_2") (pintype "input"))
      (node (ref "U8") (pin "1") (pinfunction "MD0_1") (pintype "input"))
    )
    (net (code "17") (name "/MODES") (class "Default")
      (node (ref "SW1") (pin "1") (pinfunction "1_1") (pintype "unspecified"))
      (node (ref "U1") (pin "15") (pinfunction "PA4/ADC4/OP2O1_15") (pintype "unspecified"))
    )
    (net (code "18") (name "/MRST") (class "Default")
      (node (ref "R29") (pin "1") (pinfunction "1_1") (pintype "input"))
      (node (ref "U13") (pin "23") (pinfunction "RST_23") (pintype "unspecified"))
      (node (ref "U8") (pin "16") (pinfunction "REST_16") (pintype "input"))
      (node (ref "U9") (pin "24") (pinfunction "RESET_24") (pintype "input"))
    )
    (net (code "19") (name "/PA0") (class "Default")
      (node (ref "U11") (pin "18") (pinfunction "18_18") (pintype "unspecified"))
      (node (ref "U4") (pin "10") (pinfunction "PA0-WKUP_10") (pintype "unspecified"))
    )
    (net (code "20") (name "/PA1") (class "Default")
      (node (ref "R18") (pin "1") (pinfunction "1_1") (pintype "input"))
      (node (ref "U11") (pin "20") (pinfunction "20_20") (pintype "unspecified"))
      (node (ref "U4") (pin "11") (pinfunction "PA1_11") (pintype "unspecified"))
    )
    (net (code "21") (name "/PA4") (class "Default")
      (node (ref "U11") (pin "19") (pinfunction "19_19") (pintype "unspecified"))
      (node (ref "U4") (pin "14") (pinfunction "PA4_14") (pintype "unspecified"))
    )
    (net (code "22") (name "/PA5") (class "Default")
      (node (ref "LCD1") (pin "3") (pinfunction "3_3") (pintype "unspecified"))
      (node (ref "U11") (pin "17") (pinfunction "17_17") (pintype "unspecified"))
      (node (ref "U4") (pin "15") (pinfunction "PA5_15") (pintype "unspecified"))
    )
    (net (code "23") (name "/PA6") (class "Default")
      (node (ref "U11") (pin "15") (pinfunction "15_15") (pintype "unspecified"))
      (node (ref "U4") (pin "16") (pinfunction "PA6_16") (pintype "unspecified"))
    )
    (net (code "24") (name "/PA7") (class "Default")
      (node (ref "LCD1") (pin "4") (pinfunction "4_4") (pintype "unspecified"))
      (node (ref "U11") (pin "13") (pinfunction "13_13") (pintype "unspecified"))
      (node (ref "U4") (pin "17") (pinfunction "PA7_17") (pintype "unspecified"))
    )
    (net (code "25") (name "/PA8") (class "Default")
      (node (ref "U13") (pin "22") (pinfunction "PWRC_22") (pintype "unspecified"))
      (node (ref "U4") (pin "29") (pinfunction "PA8_29") (pintype "unspecified"))
    )
    (net (code "26") (name "/PA15") (class "Default")
      (node (ref "LCD1") (pin "5") (pinfunction "5_5") (pintype "unspecified"))
      (node (ref "U4") (pin "38") (pinfunction "PA15_38") (pintype "unspecified"))
    )
    (net (code "27") (name "/PB0") (class "Default")
      (node (ref "K1") (pin "2") (pinfunction "2_2") (pintype "input"))
      (node (ref "U4") (pin "18") (pinfunction "PB0_18") (pintype "unspecified"))
    )
    (net (code "28") (name "/PB1") (class "Default")
      (node (ref "K2") (pin "2") (pinfunction "2_2") (pintype "input"))
      (node (ref "U4") (pin "19") (pinfunction "PB1_19") (pintype "unspecified"))
    )
    (net (code "29") (name "/PB3") (class "Default")
      (node (ref "LCD1") (pin "6") (pinfunction "6_6") (pintype "unspecified"))
      (node (ref "U4") (pin "39") (pinfunction "PB3_39") (pintype "unspecified"))
    )
    (net (code "30") (name "/PB4") (class "Default")
      (node (ref "LCD1") (pin "7") (pinfunction "7_7") (pintype "unspecified"))
      (node (ref "U4") (pin "40") (pinfunction "PB4_40") (pintype "unspecified"))
    )
    (net (code "31") (name "/PB5") (class "Default")
      (node (ref "LCD1") (pin "8") (pinfunction "8_8") (pintype "unspecified"))
      (node (ref "U4") (pin "41") (pinfunction "PB5_41") (pintype "unspecified"))
    )
    (net (code "32") (name "/PB6-SCL") (class "Default")
      (node (ref "H3") (pin "10") (pinfunction "10_10") (pintype "unspecified"))
      (node (ref "U4") (pin "42") (pinfunction "PB6_42") (pintype "unspecified"))
    )
    (net (code "33") (name "/PB7-SDA") (class "Default")
      (node (ref "H3") (pin "12") (pinfunction "12_12") (pintype "unspecified"))
      (node (ref "U4") (pin "43") (pinfunction "PB7_43") (pintype "unspecified"))
    )
    (net (code "34") (name "/PB8") (class "Default")
      (node (ref "R19") (pin "1") (pinfunction "1_1") (pintype "input"))
      (node (ref "U11") (pin "14") (pinfunction "14_14") (pintype "unspecified"))
      (node (ref "U4") (pin "45") (pinfunction "PB8_45") (pintype "unspecified"))
    )
    (net (code "35") (name "/PB9") (class "Default")
      (node (ref "LCD1") (pin "9") (pinfunction "9_9") (pintype "unspecified"))
      (node (ref "U4") (pin "46") (pinfunction "PB9_46") (pintype "unspecified"))
    )
    (net (code "36") (name "/PB12") (class "Default")
      (node (ref "H3") (pin "11") (pinfunction "11_11") (pintype "unspecified"))
      (node (ref "U4") (pin "25") (pinfunction "PB12_25") (pintype "unspecified"))
    )
    (net (code "37") (name "/PB13") (class "Default")
      (node (ref "H3") (pin "9") (pinfunction "9_9") (pintype "unspecified"))
      (node (ref "U4") (pin "26") (pinfunction "PB13_26") (pintype "unspecified"))
    )
    (net (code "38") (name "/PB14") (class "Default")
      (node (ref "H3") (pin "7") (pinfunction "7_7") (pintype "unspecified"))
      (node (ref "U4") (pin "27") (pinfunction "PB14_27") (pintype "unspecified"))
    )
    (net (code "39") (name "/PB15") (class "Default")
      (node (ref "H3") (pin "5") (pinfunction "5_5") (pintype "unspecified"))
      (node (ref "U4") (pin "28") (pinfunction "PB15_28") (pintype "unspecified"))
    )
    (net (code "40") (name "/PC13") (class "Default")
      (node (ref "U11") (pin "16") (pinfunction "16_16") (pintype "unspecified"))
      (node (ref "U4") (pin "2") (pinfunction "PC13-TAMPER-RTC_2") (pintype "unspecified"))
    )
    (net (code "41") (name "/RST") (class "Default")
      (node (ref "C16") (pin "2") (pinfunction "2_2") (pintype "unspecified"))
      (node (ref "R28") (pin "1") (pinfunction "1_1") (pintype "input"))
      (node (ref "SW6") (pin "2") (pinfunction "2_2") (pintype "unspecified"))
      (node (ref "U4") (pin "7") (pinfunction "NRST_7") (pintype "unspecified"))
    )
    (net (code "42") (name "/SWCLK") (class "Default")
      (node (ref "R20") (pin "1") (pinfunction "1_1") (pintype "input"))
      (node (ref "R4") (pin "2") (pinfunction "2_2") (pintype "input"))
      (node (ref "U4") (pin "37") (pinfunction "PA14_37") (pintype "unspecified"))
    )
    (net (code "43") (name "/SWDIO") (class "Default")
      (node (ref "R22") (pin "1") (pinfunction "1_1") (pintype "input"))
      (node (ref "R6") (pin "2") (pinfunction "2_2") (pintype "input"))
      (node (ref "U4") (pin "34") (pinfunction "PA13_34") (pintype "unspecified"))
    )
    (net (code "44") (name "/TYPEC_USB_D+") (class "Default")
      (node (ref "SW4") (pin "6") (pinfunction "6_6") (pintype "unspecified"))
      (node (ref "USBC1") (pin "A6") (pinfunction "DP1_A6") (pintype "input"))
      (node (ref "USBC1") (pin "B6") (pinfunction "DP2_B6") (pintype "input"))
    )
    (net (code "45") (name "/TYPEC_USB_D-") (class "Default")
      (node (ref "SW4") (pin "3") (pinfunction "3_3") (pintype "unspecified"))
      (node (ref "USBC1") (pin "A7") (pinfunction "DN1_A7") (pintype "input"))
      (node (ref "USBC1") (pin "B7") (pinfunction "DN2_B7") (pintype "input"))
    )
    (net (code "46") (name "/UART2_RX") (class "Default")
      (node (ref "R9") (pin "1") (pinfunction "1_1") (pintype "input"))
      (node (ref "U1") (pin "12") (pinfunction "PA3/ADC3/OP1O0_12") (pintype "unspecified"))
    )
    (net (code "47") (name "/UART2_TX") (class "Default")
      (node (ref "R10") (pin "1") (pinfunction "1_1") (pintype "input"))
      (node (ref "U1") (pin "11") (pinfunction "PA2/ADC2/OP2O0_11") (pintype "unspecified"))
    )
    (net (code "48") (name "/USART3_RX") (class "Default")
      (node (ref "R3") (pin "2") (pinfunction "2_2") (pintype "input"))
      (node (ref "U11") (pin "9") (pinfunction "9_9") (pintype "unspecified"))
      (node (ref "U2") (pin "1") (pinfunction "RO_1") (pintype "unspecified"))
      (node (ref "U4") (pin "22") (pinfunction "PB11_22") (pintype "unspecified"))
    )
    (net (code "49") (name "/USART3_TX") (class "Default")
      (node (ref "R8") (pin "2") (pinfunction "2_2") (pintype "input"))
      (node (ref "U11") (pin "11") (pinfunction "11_11") (pintype "unspecified"))
      (node (ref "U4") (pin "21") (pinfunction "PB10_21") (pintype "unspecified"))
    )
    (net (code "50") (name "/VDDA") (class "Default")
      (node (ref "C15") (pin "2") (pinfunction "2_2") (pintype "unspecified"))
      (node (ref "L1") (pin "1") (pinfunction "1_1") (pintype "unspecified"))
      (node (ref "U4") (pin "9") (pinfunction "VDDA_9") (pintype "unspecified"))
    )
    (net (code "51") (name "3.3V") (class "Default")
      (node (ref "C14") (pin "2") (pinfunction "2_2") (pintype "unspecified"))
      (node (ref "C3") (pin "2") (pinfunction "2_2") (pintype "unspecified"))
      (node (ref "C5") (pin "1") (pinfunction "1_1") (pintype "unspecified"))
      (node (ref "C9") (pin "1") (pinfunction "1_1") (pintype "unspecified"))
      (node (ref "H3") (pin "13") (pinfunction "13_13") (pintype "unspecified"))
      (node (ref "H3") (pin "14") (pinfunction "14_14") (pintype "unspecified"))
      (node (ref "L1") (pin "2") (pinfunction "2_2") (pintype "unspecified"))
      (node (ref "LCD1") (pin "10") (pinfunction "10_10") (pintype "unspecified"))
      (node (ref "LED1") (pin "2") (pinfunction "A_2") (pintype "unspecified"))
      (node (ref "LED2") (pin "2") (pinfunction "A_2") (pintype "unspecified"))
      (node (ref "NWK-LED1") (pin "2") (pinfunction "A_2") (pintype "input"))
      (node (ref "R15") (pin "2") (pinfunction "2_2") (pintype "input"))
      (node (ref "R2") (pin "2") (pinfunction "2_2") (pintype "input"))
      (node (ref "R20") (pin "2") (pinfunction "2_2") (pintype "input"))
      (node (ref "R22") (pin "2") (pinfunction "2_2") (pintype "input"))
      (node (ref "R24") (pin "1") (pinfunction "1_1") (pintype "input"))
      (node (ref "R26") (pin "1") (pinfunction "1_1") (pintype "input"))
      (node (ref "R28") (pin "2") (pinfunction "2_2") (pintype "input"))
      (node (ref "R3") (pin "1") (pinfunction "1_1") (pintype "input"))
      (node (ref "RUN-LED1") (pin "2") (pinfunction "A_2") (pintype "input"))
      (node (ref "SW7") (pin "1") (pinfunction "1_1") (pintype "input"))
      (node (ref "U11") (pin "5") (pinfunction "5_5") (pintype "unspecified"))
      (node (ref "U11") (pin "6") (pinfunction "6_6") (pintype "unspecified"))
      (node (ref "U11") (pin "7") (pinfunction "7_7") (pintype "unspecified"))
      (node (ref "U11") (pin "8") (pinfunction "8_8") (pintype "unspecified"))
      (node (ref "U13") (pin "1") (pinfunction "VCC_1") (pintype "unspecified"))
      (node (ref "U2") (pin "8") (pinfunction "VCC_8") (pintype "unspecified"))
      (node (ref "U4") (pin "1") (pinfunction "VBAT_1") (pintype "unspecified"))
      (node (ref "U4") (pin "24") (pinfunction "VDD_1_24") (pintype "unspecified"))
      (node (ref "U4") (pin "36") (pinfunction "VDD_2_36") (pintype "unspecified"))
      (node (ref "U4") (pin "48") (pinfunction "VDD_3_48") (pintype "unspecified"))
      (node (ref "U5") (pin "1") (pinfunction "VOUT_1") (pintype "unspecified"))
      (node (ref "U8") (pin "6") (pinfunction "VCC_6") (pintype "input"))
      (node (ref "U9") (pin "2") (pinfunction "VCC_2") (pintype "input"))
    )
    (net (code "52") (name "3.3VIN") (class "Default")
      (node (ref "C12") (pin "2") (pinfunction "2_2") (pintype "input"))
      (node (ref "C13") (pin "2") (pinfunction "2_2") (pintype "input"))
      (node (ref "C2") (pin "2") (pinfunction "2_2") (pintype "unspecified"))
      (node (ref "R1") (pin "1") (pinfunction "1_1") (pintype "input"))
      (node (ref "R16") (pin "2") (pinfunction "2_2") (pintype "input"))
      (node (ref "SW2") (pin "2") (pinfunction "2_2") (pintype "unspecified"))
      (node (ref "U1") (pin "6") (pinfunction "VDD_6") (pintype "unspecified"))
      (node (ref "U5") (pin "6") (pinfunction "VIN_6") (pintype "unspecified"))
      (node (ref "U6") (pin "3") (pinfunction "VOUT_3") (pintype "input"))
    )
    (net (code "53") (name "5V") (class "Default")
      (node (ref "C1") (pin "2") (pinfunction "2_2") (pintype "unspecified"))
      (node (ref "H3") (pin "17") (pinfunction "17_17") (pintype "unspecified"))
      (node (ref "H3") (pin "18") (pinfunction "18_18") (pintype "unspecified"))
      (node (ref "LCD1") (pin "2") (pinfunction "2_2") (pintype "unspecified"))
      (node (ref "R33") (pin "1") (pinfunction "1_1") (pintype "input"))
      (node (ref "U10") (pin "3") (pinfunction "OUT+_3") (pintype "input"))
      (node (ref "U11") (pin "1") (pinfunction "1_1") (pintype "unspecified"))
      (node (ref "U11") (pin "2") (pinfunction "2_2") (pintype "unspecified"))
      (node (ref "U14") (pin "6") (pinfunction "VCC_6") (pintype "input"))
      (node (ref "U3") (pin "1") (pinfunction "VOUT_1") (pintype "unspecified"))
    )
    (net (code "54") (name "5VIN") (class "Default")
      (node (ref "C10") (pin "2") (pinfunction "2_2") (pintype "input"))
      (node (ref "C11") (pin "2") (pinfunction "2_2") (pintype "input"))
      (node (ref "SW3") (pin "3") (pinfunction "3_3") (pintype "unspecified"))
      (node (ref "SW3") (pin "6") (pinfunction "6_6") (pintype "unspecified"))
      (node (ref "U3") (pin "6") (pinfunction "VIN_6") (pintype "unspecified"))
      (node (ref "U6") (pin "1") (pinfunction "VIN_1") (pintype "input"))
    )
    (net (code "55") (name "12V") (class "Default")
      (node (ref "H1") (pin "1") (pinfunction "1_1") (pintype "unspecified"))
      (node (ref "H1") (pin "2") (pinfunction "2_2") (pintype "unspecified"))
      (node (ref "H2") (pin "1") (pinfunction "1_1") (pintype "unspecified"))
      (node (ref "H2") (pin "2") (pinfunction "2_2") (pintype "unspecified"))
      (node (ref "H2") (pin "3") (pinfunction "3_3") (pintype "unspecified"))
      (node (ref "H2") (pin "4") (pinfunction "4_4") (pintype "unspecified"))
      (node (ref "R34") (pin "1") (pinfunction "1_1") (pintype "input"))
      (node (ref "U10") (pin "1") (pinfunction "IN+_1") (pintype "input"))
    )
    (net (code "56") (name "485-A") (class "Default")
      (node (ref "H1") (pin "6") (pinfunction "6_6") (pintype "unspecified"))
      (node (ref "R7") (pin "1") (pinfunction "1_1") (pintype "input"))
      (node (ref "U2") (pin "6") (pinfunction "A_6") (pintype "unspecified"))
    )
    (net (code "57") (name "485-B") (class "Default")
      (node (ref "H1") (pin "8") (pinfunction "8_8") (pintype "unspecified"))
      (node (ref "R7") (pin "2") (pinfunction "2_2") (pintype "input"))
      (node (ref "U2") (pin "7") (pinfunction "B_7") (pintype "unspecified"))
    )
    (net (code "58") (name "COMM_RX") (class "Default")
      (node (ref "K3") (pin "10") (pinfunction "10_10") (pintype "input"))
      (node (ref "K3") (pin "9") (pinfunction "9_9") (pintype "input"))
      (node (ref "U11") (pin "12") (pinfunction "12_12") (pintype "unspecified"))
      (node (ref "U13") (pin "20") (pinfunction "RXD_20") (pintype "unspecified"))
      (node (ref "U14") (pin "3") (pinfunction "RXD_3") (pintype "input"))
      (node (ref "U8") (pin "3") (pinfunction "RXD_3") (pintype "input"))
      (node (ref "U9") (pin "11") (pinfunction "P1.4_11") (pintype "input"))
    )
    (net (code "59") (name "COMM_TX") (class "Default")
      (node (ref "K3") (pin "3") (pinfunction "3_3") (pintype "input"))
      (node (ref "K3") (pin "4") (pinfunction "4_4") (pintype "input"))
      (node (ref "U11") (pin "10") (pinfunction "10_10") (pintype "unspecified"))
      (node (ref "U13") (pin "19") (pinfunction "TXD_19") (pintype "unspecified"))
      (node (ref "U14") (pin "4") (pinfunction "TXD_4") (pintype "input"))
      (node (ref "U8") (pin "4") (pinfunction "TXD_4") (pintype "input"))
      (node (ref "U9") (pin "10") (pinfunction "P1.5_10") (pintype "input"))
    )
    (net (code "60") (name "DAP_RX") (class "Default")
      (node (ref "K3") (pin "5") (pinfunction "5_5") (pintype "input"))
      (node (ref "R9") (pin "2") (pinfunction "2_2") (pintype "input"))
    )
    (net (code "61") (name "DAP_TX") (class "Default")
      (node (ref "K3") (pin "11") (pinfunction "11_11") (pintype "input"))
      (node (ref "R10") (pin "2") (pinfunction "2_2") (pintype "input"))
    )
    (net (code "62") (name "GND") (class "Default")
      (node (ref "C1") (pin "1") (pinfunction "1_1") (pintype "unspecified"))
      (node (ref "C10") (pin "1") (pinfunction "1_1") (pintype "input"))
      (node (ref "C11") (pin "1") (pinfunction "1_1") (pintype "input"))
      (node (ref "C12") (pin "1") (pinfunction "1_1") (pintype "input"))
      (node (ref "C13") (pin "1") (pinfunction "1_1") (pintype "input"))
      (node (ref "C14") (pin "1") (pinfunction "1_1") (pintype "unspecified"))
      (node (ref "C15") (pin "1") (pinfunction "1_1") (pintype "unspecified"))
      (node (ref "C16") (pin "1") (pinfunction "1_1") (pintype "unspecified"))
      (node (ref "C2") (pin "1") (pinfunction "1_1") (pintype "unspecified"))
      (node (ref "C3") (pin "1") (pinfunction "1_1") (pintype "unspecified"))
      (node (ref "C4") (pin "1") (pinfunction "1_1") (pintype "unspecified"))
      (node (ref "C5") (pin "2") (pinfunction "2_2") (pintype "unspecified"))
      (node (ref "C6") (pin "1") (pinfunction "1_1") (pintype "unspecified"))
      (node (ref "C7") (pin "2") (pinfunction "2_2") (pintype "unspecified"))
      (node (ref "C8") (pin "2") (pinfunction "2_2") (pintype "unspecified"))
      (node (ref "C9") (pin "2") (pinfunction "2_2") (pintype "unspecified"))
      (node (ref "CN1") (pin "2") (pinfunction "2_2") (pintype "unspecified"))
      (node (ref "H1") (pin "10") (pinfunction "10_10") (pintype "unspecified"))
      (node (ref "H1") (pin "9") (pinfunction "9_9") (pintype "unspecified"))
      (node (ref "H3") (pin "1") (pinfunction "1_1") (pintype "unspecified"))
      (node (ref "H3") (pin "2") (pinfunction "2_2") (pintype "unspecified"))
      (node (ref "H3") (pin "3") (pinfunction "3_3") (pintype "unspecified"))
      (node (ref "H3") (pin "4") (pinfunction "4_4") (pintype "unspecified"))
      (node (ref "K1") (pin "1") (pinfunction "1_1") (pintype "input"))
      (node (ref "K2") (pin "1") (pinfunction "1_1") (pintype "input"))
      (node (ref "L2") (pin "1") (pinfunction "1_1") (pintype "unspecified"))
      (node (ref "L3") (pin "1") (pinfunction "1_1") (pintype "unspecified"))
      (node (ref "L4") (pin "1") (pinfunction "1_1") (pintype "unspecified"))
      (node (ref "LCD1") (pin "1") (pinfunction "1_1") (pintype "unspecified"))
      (node (ref "LED3") (pin "1") (pinfunction "K_1") (pintype "unspecified"))
      (node (ref "NWK-LED2") (pin "1") (pinfunction "K_1") (pintype "input"))
      (node (ref "Q1") (pin "2") (pinfunction "E_2") (pintype "unspecified"))
      (node (ref "R11") (pin "1") (pinfunction "1_1") (pintype "input"))
      (node (ref "R12") (pin "1") (pinfunction "1_1") (pintype "input"))
      (node (ref "R13") (pin "1") (pinfunction "1_1") (pintype "input"))
      (node (ref "R14") (pin "2") (pinfunction "2_2") (pintype "input"))
      (node (ref "R21") (pin "1") (pinfunction "1_1") (pintype "input"))
      (node (ref "R25") (pin "2") (pinfunction "2_2") (pintype "input"))
      (node (ref "R27") (pin "2") (pinfunction "2_2") (pintype "input"))
      (node (ref "R30") (pin "1") (pinfunction "1_1") (pintype "input"))
      (node (ref "RUN-LED2") (pin "1") (pinfunction "K_1") (pintype "input"))
      (node (ref "SW1") (pin "2") (pinfunction "2_2") (pintype "unspecified"))
      (node (ref "SW5") (pin "2") (pinfunction "2_2") (pintype "unspecified"))
      (node (ref "SW6") (pin "1") (pinfunction "1_1") (pintype "unspecified"))
      (node (ref "SW7") (pin "3") (pinfunction "3_3") (pintype "input"))
      (node (ref "SW7") (pin "4") (pinfunction "4_4") (pintype "input"))
      (node (ref "U1") (pin "7") (pinfunction "VSS_7") (pintype "unspecified"))
      (node (ref "U10") (pin "2") (pinfunction "IN-_2") (pintype "input"))
      (node (ref "U10") (pin "4") (pinfunction "OUT-_4") (pintype "input"))
      (node (ref "U11") (pin "21") (pinfunction "21_21") (pintype "unspecified"))
      (node (ref "U11") (pin "22") (pinfunction "22_22") (pintype "unspecified"))
      (node (ref "U11") (pin "23") (pinfunction "23_23") (pintype "unspecified"))
      (node (ref "U11") (pin "24") (pinfunction "24_24") (pintype "unspecified"))
      (node (ref "U13") (pin "24") (pinfunction "GND_24") (pintype "unspecified"))
      (node (ref "U14") (pin "5") (pinfunction "GND_5") (pintype "input"))
      (node (ref "U2") (pin "4") (pinfunction "DI_4") (pintype "unspecified"))
      (node (ref "U2") (pin "5") (pinfunction "GND_5") (pintype "unspecified"))
      (node (ref "U3") (pin "2") (pinfunction "GND_2") (pintype "unspecified"))
      (node (ref "U4") (pin "23") (pinfunction "VSS_1_23") (pintype "unspecified"))
      (node (ref "U4") (pin "35") (pinfunction "VSS_2_35") (pintype "unspecified"))
      (node (ref "U4") (pin "47") (pinfunction "VSS_3_47") (pintype "unspecified"))
      (node (ref "U4") (pin "8") (pinfunction "VSSA_8") (pintype "unspecified"))
      (node (ref "U5") (pin "2") (pinfunction "GND_2") (pintype "unspecified"))
      (node (ref "U6") (pin "2") (pinfunction "GND_2") (pintype "input"))
      (node (ref "U6") (pin "4") (pinfunction "GND_4") (pintype "input"))
      (node (ref "U8") (pin "13") (pinfunction "GND_13") (pintype "input"))
      (node (ref "U8") (pin "2") (pinfunction "MD1_2") (pintype "input"))
      (node (ref "U8") (pin "7") (pinfunction "GND_7") (pintype "input"))
      (node (ref "U8") (pin "9") (pinfunction "GND_9") (pintype "input"))
      (node (ref "U9") (pin "1") (pinfunction "GND_1") (pintype "input"))
      (node (ref "USBC1") (pin "A1") (pinfunction "GND_A1") (pintype "input"))
      (node (ref "USBC1") (pin "A12") (pinfunction "GND_A12") (pintype "input"))
      (node (ref "USBC1") (pin "B1") (pinfunction "GND_B1") (pintype "input"))
      (node (ref "USBC1") (pin "B12") (pinfunction "GND_B12") (pintype "input"))
    )
    (net (code "63") (name "M_USBD+") (class "Default")
      (node (ref "H1") (pin "5") (pinfunction "5_5") (pintype "unspecified"))
      (node (ref "SW4") (pin "4") (pinfunction "4_4") (pintype "unspecified"))
    )
    (net (code "64") (name "M_USBD-") (class "Default")
      (node (ref "H1") (pin "7") (pinfunction "7_7") (pintype "unspecified"))
      (node (ref "SW4") (pin "1") (pinfunction "1_1") (pintype "unspecified"))
    )
    (net (code "65") (name "M_VCC") (class "Default")
      (node (ref "F2") (pin "1") (pinfunction "1_1") (pintype "input"))
      (node (ref "H1") (pin "11") (pinfunction "11_11") (pintype "unspecified"))
      (node (ref "H1") (pin "12") (pinfunction "12_12") (pintype "unspecified"))
    )
    (net (code "66") (name "Net-(C17-Pad2)") (class "Default")
      (node (ref "C17") (pin "2") (pinfunction "2_2") (pintype "unspecified"))
      (node (ref "L3") (pin "2") (pinfunction "2_2") (pintype "unspecified"))
      (node (ref "U12") (pin "1") (pinfunction "1_1") (pintype "unspecified"))
    )
    (net (code "67") (name "Net-(CN1-Pad1)") (class "Default")
      (node (ref "CN1") (pin "1") (pinfunction "1_1") (pintype "unspecified"))
      (node (ref "R33") (pin "2") (pinfunction "2_2") (pintype "input"))
      (node (ref "R34") (pin "2") (pinfunction "2_2") (pintype "input"))
    )
    (net (code "68") (name "Net-(F1-Pad2)") (class "Default")
      (node (ref "F1") (pin "2") (pinfunction "2_2") (pintype "input"))
      (node (ref "F2") (pin "2") (pinfunction "2_2") (pintype "input"))
      (node (ref "SW3") (pin "2") (pinfunction "2_2") (pintype "unspecified"))
      (node (ref "SW3") (pin "5") (pinfunction "5_5") (pintype "unspecified"))
    )
    (net (code "69") (name "Net-(L4-Pad2)") (class "Default")
      (node (ref "L4") (pin "2") (pinfunction "2_2") (pintype "unspecified"))
      (node (ref "U12") (pin "2") (pinfunction "2_2") (pintype "unspecified"))
    )
    (net (code "70") (name "Net-(LED1-K)") (class "Default")
      (node (ref "LED1") (pin "1") (pinfunction "K_1") (pintype "unspecified"))
      (node (ref "R18") (pin "2") (pinfunction "2_2") (pintype "input"))
    )
    (net (code "71") (name "Net-(LED2-K)") (class "Default")
      (node (ref "LED2") (pin "1") (pinfunction "K_1") (pintype "unspecified"))
      (node (ref "R19") (pin "2") (pinfunction "2_2") (pintype "input"))
    )
    (net (code "72") (name "Net-(LED3-A)") (class "Default")
      (node (ref "LED3") (pin "2") (pinfunction "A_2") (pintype "unspecified"))
      (node (ref "R15") (pin "1") (pinfunction "1_1") (pintype "input"))
    )
    (net (code "73") (name "Net-(LED4-A)") (class "Default")
      (node (ref "LED4") (pin "2") (pinfunction "A_2") (pintype "unspecified"))
      (node (ref "R16") (pin "1") (pinfunction "1_1") (pintype "input"))
    )
    (net (code "74") (name "Net-(NWK-LED1-K)") (class "Default")
      (node (ref "NWK-LED1") (pin "1") (pinfunction "K_1") (pintype "input"))
      (node (ref "R31") (pin "2") (pinfunction "2_2") (pintype "input"))
    )
    (net (code "75") (name "Net-(NWK-LED2-A)") (class "Default")
      (node (ref "NWK-LED2") (pin "2") (pinfunction "A_2") (pintype "input"))
      (node (ref "R35") (pin "2") (pinfunction "2_2") (pintype "input"))
    )
    (net (code "76") (name "Net-(Q1-B)") (class "Default")
      (node (ref "Q1") (pin "1") (pinfunction "B_1") (pintype "unspecified"))
      (node (ref "R8") (pin "1") (pinfunction "1_1") (pintype "input"))
    )
    (net (code "77") (name "Net-(Q1-C)") (class "Default")
      (node (ref "Q1") (pin "3") (pinfunction "C_3") (pintype "unspecified"))
      (node (ref "R2") (pin "1") (pinfunction "1_1") (pintype "input"))
      (node (ref "U2") (pin "2") (pinfunction "#RE_2") (pintype "unspecified"))
      (node (ref "U2") (pin "3") (pinfunction "DE_3") (pintype "unspecified"))
    )
    (net (code "78") (name "Net-(R25-Pad1)") (class "Default")
      (node (ref "R25") (pin "1") (pinfunction "1_1") (pintype "input"))
      (node (ref "U7") (pin "4") (pinfunction "4_4") (pintype "unspecified"))
    )
    (net (code "79") (name "Net-(R27-Pad1)") (class "Default")
      (node (ref "R27") (pin "1") (pinfunction "1_1") (pintype "input"))
      (node (ref "U7") (pin "3") (pinfunction "3_3") (pintype "unspecified"))
    )
    (net (code "80") (name "Net-(R29-Pad2)") (class "Default")
      (node (ref "R29") (pin "2") (pinfunction "2_2") (pintype "input"))
      (node (ref "SW5") (pin "1") (pinfunction "1_1") (pintype "unspecified"))
    )
    (net (code "81") (name "Net-(RUN-LED1-K)") (class "Default")
      (node (ref "R32") (pin "2") (pinfunction "2_2") (pintype "input"))
      (node (ref "RUN-LED1") (pin "1") (pinfunction "K_1") (pintype "input"))
    )
    (net (code "82") (name "Net-(RUN-LED2-A)") (class "Default")
      (node (ref "R36") (pin "2") (pinfunction "2_2") (pintype "input"))
      (node (ref "RUN-LED2") (pin "2") (pinfunction "A_2") (pintype "input"))
    )
    (net (code "83") (name "Net-(U1-PA11{slash}U1DM{slash}CAN_RX{slash}TIM1_CH4)") (class "Default")
      (node (ref "R1") (pin "2") (pinfunction "2_2") (pintype "input"))
      (node (ref "U1") (pin "27") (pinfunction "PA11/U1DM/CAN_RX/TIM1_CH4_27") (pintype "unspecified"))
    )
    (net (code "84") (name "Net-(U3-ISET)") (class "Default")
      (node (ref "R11") (pin "2") (pinfunction "2_2") (pintype "input"))
      (node (ref "U3") (pin "5") (pinfunction "ISET_5") (pintype "unspecified"))
    )
    (net (code "85") (name "Net-(U4-PC14-OSC32_IN)") (class "Default")
      (node (ref "C4") (pin "2") (pinfunction "2_2") (pintype "unspecified"))
      (node (ref "U4") (pin "3") (pinfunction "PC14-OSC32_IN_3") (pintype "unspecified"))
      (node (ref "X1") (pin "2") (pinfunction "OSC2_2") (pintype "input"))
    )
    (net (code "86") (name "Net-(U4-PC15-OSC32_OUT)") (class "Default")
      (node (ref "C6") (pin "2") (pinfunction "2_2") (pintype "unspecified"))
      (node (ref "U4") (pin "4") (pinfunction "PC15-OSC32_OUT_4") (pintype "unspecified"))
      (node (ref "X1") (pin "1") (pinfunction "OSC1_1") (pintype "input"))
    )
    (net (code "87") (name "Net-(U4-PD0-OSC_IN)") (class "Default")
      (node (ref "C7") (pin "1") (pinfunction "1_1") (pintype "unspecified"))
      (node (ref "R17") (pin "2") (pinfunction "2_2") (pintype "input"))
      (node (ref "U4") (pin "5") (pinfunction "PD0-OSC_IN_5") (pintype "unspecified"))
      (node (ref "X2") (pin "2") (pinfunction "OSC2_2") (pintype "input"))
    )
    (net (code "88") (name "Net-(U4-PD1-OSC_OUT)") (class "Default")
      (node (ref "C8") (pin "1") (pinfunction "1_1") (pintype "unspecified"))
      (node (ref "R17") (pin "1") (pinfunction "1_1") (pintype "input"))
      (node (ref "U4") (pin "6") (pinfunction "PD1-OSC_OUT_6") (pintype "unspecified"))
      (node (ref "X2") (pin "1") (pinfunction "OSC1_1") (pintype "input"))
    )
    (net (code "89") (name "Net-(U5-ISET)") (class "Default")
      (node (ref "R21") (pin "2") (pinfunction "2_2") (pintype "input"))
      (node (ref "U5") (pin "5") (pinfunction "ISET_5") (pintype "unspecified"))
    )
    (net (code "90") (name "Net-(U9-P1.2)") (class "Default")
      (node (ref "R31") (pin "1") (pinfunction "1_1") (pintype "input"))
      (node (ref "U9") (pin "13") (pinfunction "P1.2_13") (pintype "input"))
    )
    (net (code "91") (name "Net-(U9-P1.3)") (class "Default")
      (node (ref "R32") (pin "1") (pinfunction "1_1") (pintype "input"))
      (node (ref "U9") (pin "12") (pinfunction "P1.3_12") (pintype "input"))
    )
    (net (code "92") (name "Net-(U9-P1.6)") (class "Default")
      (node (ref "R30") (pin "2") (pinfunction "2_2") (pintype "input"))
      (node (ref "U9") (pin "7") (pinfunction "P1.6_7") (pintype "input"))
    )
    (net (code "93") (name "Net-(U13-STAT)") (class "Default")
      (node (ref "R36") (pin "1") (pinfunction "1_1") (pintype "input"))
      (node (ref "U13") (pin "6") (pinfunction "STAT_6") (pintype "unspecified"))
    )
    (net (code "94") (name "Net-(USBC1-CC1)") (class "Default")
      (node (ref "R14") (pin "1") (pinfunction "1_1") (pintype "input"))
      (node (ref "USBC1") (pin "A5") (pinfunction "CC1_A5") (pintype "input"))
    )
    (net (code "95") (name "Net-(USBC1-CC2)") (class "Default")
      (node (ref "R12") (pin "2") (pinfunction "2_2") (pintype "input"))
      (node (ref "USBC1") (pin "B5") (pinfunction "CC2_B5") (pintype "input"))
    )
    (net (code "96") (name "USART1_RX") (class "Default")
      (node (ref "K3") (pin "12") (pinfunction "12_12") (pintype "input"))
      (node (ref "U4") (pin "31") (pinfunction "PA10_31") (pintype "unspecified"))
    )
    (net (code "97") (name "USART1_TX") (class "Default")
      (node (ref "K3") (pin "6") (pinfunction "6_6") (pintype "input"))
      (node (ref "U4") (pin "30") (pinfunction "PA9_30") (pintype "unspecified"))
    )
    (net (code "98") (name "USART2_RX") (class "Default")
      (node (ref "K3") (pin "2") (pinfunction "2_2") (pintype "input"))
      (node (ref "U4") (pin "13") (pinfunction "PA3_13") (pintype "unspecified"))
    )
    (net (code "99") (name "USART2_TX") (class "Default")
      (node (ref "K3") (pin "8") (pinfunction "8_8") (pintype "input"))
      (node (ref "U4") (pin "12") (pinfunction "PA2_12") (pintype "unspecified"))
    )
    (net (code "100") (name "VBUS") (class "Default")
      (node (ref "F1") (pin "1") (pinfunction "1_1") (pintype "input"))
      (node (ref "USBC1") (pin "A4") (pinfunction "VBUS_A4") (pintype "input"))
      (node (ref "USBC1") (pin "A9") (pinfunction "VBUS_A9") (pintype "input"))
      (node (ref "USBC1") (pin "B4") (pinfunction "VBUS_B4") (pintype "input"))
      (node (ref "USBC1") (pin "B9") (pinfunction "VBUS_B9") (pintype "input"))
    )
    (net (code "101") (name "unconnected-(DIP1-Pad1)") (class "Default")
      (node (ref "DIP1") (pin "1") (pinfunction "1_1") (pintype "input+no_connect"))
    )
    (net (code "102") (name "unconnected-(DIP2-Pad1)") (class "Default")
      (node (ref "DIP2") (pin "1") (pinfunction "1_1") (pintype "input+no_connect"))
    )
    (net (code "103") (name "unconnected-(DIP3-Pad1)") (class "Default")
      (node (ref "DIP3") (pin "1") (pinfunction "1_1") (pintype "input+no_connect"))
    )
    (net (code "104") (name "unconnected-(DIP4-Pad1)") (class "Default")
      (node (ref "DIP4") (pin "1") (pinfunction "1_1") (pintype "input+no_connect"))
    )
    (net (code "105") (name "unconnected-(H1-Pad3)") (class "Default")
      (node (ref "H1") (pin "3") (pinfunction "3_3") (pintype "unspecified+no_connect"))
    )
    (net (code "106") (name "unconnected-(H1-Pad4)") (class "Default")
      (node (ref "H1") (pin "4") (pinfunction "4_4") (pintype "unspecified+no_connect"))
    )
    (net (code "107") (name "unconnected-(H3-Pad15)") (class "Default")
      (node (ref "H3") (pin "15") (pinfunction "15_15") (pintype "unspecified+no_connect"))
    )
    (net (code "108") (name "unconnected-(H3-Pad16)") (class "Default")
      (node (ref "H3") (pin "16") (pinfunction "16_16") (pintype "unspecified+no_connect"))
    )
    (net (code "109") (name "unconnected-(H3-Pad19)") (class "Default")
      (node (ref "H3") (pin "19") (pinfunction "19_19") (pintype "unspecified+no_connect"))
    )
    (net (code "110") (name "unconnected-(H3-Pad20)") (class "Default")
      (node (ref "H3") (pin "20") (pinfunction "20_20") (pintype "unspecified+no_connect"))
    )
    (net (code "111") (name "unconnected-(K3-Pad1)") (class "Default")
      (node (ref "K3") (pin "1") (pinfunction "1_1") (pintype "input+no_connect"))
    )
    (net (code "112") (name "unconnected-(K3-Pad7)") (class "Default")
      (node (ref "K3") (pin "7") (pinfunction "7_7") (pintype "input+no_connect"))
    )
    (net (code "113") (name "unconnected-(SW3-Pad1)") (class "Default")
      (node (ref "SW3") (pin "1") (pinfunction "1_1") (pintype "unspecified+no_connect"))
    )
    (net (code "114") (name "unconnected-(SW3-Pad4)") (class "Default")
      (node (ref "SW3") (pin "4") (pinfunction "4_4") (pintype "unspecified+no_connect"))
    )
    (net (code "115") (name "unconnected-(U1-NRST-Pad8)") (class "Default")
      (node (ref "U1") (pin "8") (pinfunction "NRST_8") (pintype "unspecified+no_connect"))
    )
    (net (code "116") (name "unconnected-(U1-PA6{slash}ADC6{slash}OP1N1-Pad13)") (class "Default")
      (node (ref "U1") (pin "13") (pinfunction "PA6/ADC6/OP1N1_13") (pintype "unspecified+no_connect"))
    )
    (net (code "117") (name "unconnected-(U1-PA7{slash}ADC7{slash}OP2P1-Pad17)") (class "Default")
      (node (ref "U1") (pin "17") (pinfunction "PA7/ADC7/OP2P1_17") (pintype "unspecified+no_connect"))
    )
    (net (code "118") (name "unconnected-(U1-PA8{slash}TIM1_CH1-Pad24)") (class "Default")
      (node (ref "U1") (pin "24") (pinfunction "PA8/TIM1_CH1_24") (pintype "unspecified+no_connect"))
    )
    (net (code "119") (name "unconnected-(U1-PA10{slash}TIM1_CH3-Pad26)") (class "Default")
      (node (ref "U1") (pin "26") (pinfunction "PA10/TIM1_CH3_26") (pintype "unspecified+no_connect"))
    )
    (net (code "120") (name "unconnected-(U1-PB0{slash}ADC8{slash}OP1P1-Pad14)") (class "Default")
      (node (ref "U1") (pin "14") (pinfunction "PB0/ADC8/OP1P1_14") (pintype "unspecified+no_connect"))
    )
    (net (code "121") (name "unconnected-(U1-PB1{slash}ADC9{slash}OP1O1{slash}PB12{slash}TIM1_BKIN-Pad20)") (class "Default")
      (node (ref "U1") (pin "20") (pinfunction "PB1/ADC9/OP1O1/PB12/TIM1_BKIN_20") (pintype "unspecified+no_connect"))
    )
    (net (code "122") (name "unconnected-(U1-PB8{slash}TIM4_CH3-Pad5)") (class "Default")
      (node (ref "U1") (pin "5") (pinfunction "PB8/TIM4_CH3_5") (pintype "unspecified+no_connect"))
    )
    (net (code "123") (name "unconnected-(U1-PB10{slash}OP2N0-Pad18)") (class "Default")
      (node (ref "U1") (pin "18") (pinfunction "PB10/OP2N0_18") (pintype "unspecified+no_connect"))
    )
    (net (code "124") (name "unconnected-(U1-PB11{slash}OP1N0-Pad19)") (class "Default")
      (node (ref "U1") (pin "19") (pinfunction "PB11/OP1N0_19") (pintype "unspecified+no_connect"))
    )
    (net (code "125") (name "unconnected-(U1-PB13{slash}TIM1_CH1N-Pad21)") (class "Default")
      (node (ref "U1") (pin "21") (pinfunction "PB13/TIM1_CH1N_21") (pintype "unspecified+no_connect"))
    )
    (net (code "126") (name "unconnected-(U1-PB14{slash}OP2P0{slash}TIM1_CH2N-Pad22)") (class "Default")
      (node (ref "U1") (pin "22") (pinfunction "PB14/OP2P0/TIM1_CH2N_22") (pintype "unspecified+no_connect"))
    )
    (net (code "127") (name "unconnected-(U1-PB15{slash}OP1P0{slash}TIM1_CH3N-Pad23)") (class "Default")
      (node (ref "U1") (pin "23") (pinfunction "PB15/OP1P0/TIM1_CH3N_23") (pintype "unspecified+no_connect"))
    )
    (net (code "128") (name "unconnected-(U3-FLAG#-Pad3)") (class "Default")
      (node (ref "U3") (pin "3") (pinfunction "FLAG#_3") (pintype "unspecified+no_connect"))
    )
    (net (code "129") (name "unconnected-(U5-FLAG#-Pad3)") (class "Default")
      (node (ref "U5") (pin "3") (pinfunction "FLAG#_3") (pintype "unspecified+no_connect"))
    )
    (net (code "130") (name "unconnected-(U8-BOOT-Pad15)") (class "Default")
      (node (ref "U8") (pin "15") (pinfunction "BOOT_15") (pintype "input+no_connect"))
    )
    (net (code "131") (name "unconnected-(U8-NC-Pad10)") (class "Default")
      (node (ref "U8") (pin "10") (pinfunction "NC_10") (pintype "input+no_connect"))
    )
    (net (code "132") (name "unconnected-(U8-NC-Pad11)") (class "Default")
      (node (ref "U8") (pin "11") (pinfunction "NC_11") (pintype "input+no_connect"))
    )
    (net (code "133") (name "unconnected-(U8-NC-Pad12)") (class "Default")
      (node (ref "U8") (pin "12") (pinfunction "NC_12") (pintype "input+no_connect"))
    )
    (net (code "134") (name "unconnected-(U8-PA2-Pad14)") (class "Default")
      (node (ref "U8") (pin "14") (pinfunction "PA2_14") (pintype "input+no_connect"))
    )
    (net (code "135") (name "unconnected-(U8-SWCLK-Pad18)") (class "Default")
      (node (ref "U8") (pin "18") (pinfunction "SWCLK_18") (pintype "input+no_connect"))
    )
    (net (code "136") (name "unconnected-(U8-SWDIO-Pad17)") (class "Default")
      (node (ref "U8") (pin "17") (pinfunction "SWDIO_17") (pintype "input+no_connect"))
    )
    (net (code "137") (name "unconnected-(U9-NC-Pad8)") (class "Default")
      (node (ref "U9") (pin "8") (pinfunction "NC_8") (pintype "input+no_connect"))
    )
    (net (code "138") (name "unconnected-(U9-NC-Pad9)") (class "Default")
      (node (ref "U9") (pin "9") (pinfunction "NC_9") (pintype "input+no_connect"))
    )
    (net (code "139") (name "unconnected-(U9-P0.0-Pad23)") (class "Default")
      (node (ref "U9") (pin "23") (pinfunction "P0.0_23") (pintype "input+no_connect"))
    )
    (net (code "140") (name "unconnected-(U9-P0.1-Pad22)") (class "Default")
      (node (ref "U9") (pin "22") (pinfunction "P0.1_22") (pintype "input+no_connect"))
    )
    (net (code "141") (name "unconnected-(U9-P0.2-Pad21)") (class "Default")
      (node (ref "U9") (pin "21") (pinfunction "P0.2_21") (pintype "input+no_connect"))
    )
    (net (code "142") (name "unconnected-(U9-P0.3-Pad20)") (class "Default")
      (node (ref "U9") (pin "20") (pinfunction "P0.3_20") (pintype "input+no_connect"))
    )
    (net (code "143") (name "unconnected-(U9-P0.4-Pad19)") (class "Default")
      (node (ref "U9") (pin "19") (pinfunction "P0.4_19") (pintype "input+no_connect"))
    )
    (net (code "144") (name "unconnected-(U9-P0.5-Pad18)") (class "Default")
      (node (ref "U9") (pin "18") (pinfunction "P0.5_18") (pintype "input+no_connect"))
    )
    (net (code "145") (name "unconnected-(U9-P0.6-Pad17)") (class "Default")
      (node (ref "U9") (pin "17") (pinfunction "P0.6_17") (pintype "input+no_connect"))
    )
    (net (code "146") (name "unconnected-(U9-P0.7-Pad16)") (class "Default")
      (node (ref "U9") (pin "16") (pinfunction "P0.7_16") (pintype "input+no_connect"))
    )
    (net (code "147") (name "unconnected-(U9-P1.0-Pad15)") (class "Default")
      (node (ref "U9") (pin "15") (pinfunction "P1.0_15") (pintype "input+no_connect"))
    )
    (net (code "148") (name "unconnected-(U9-P1.1-Pad14)") (class "Default")
      (node (ref "U9") (pin "14") (pinfunction "P1.1_14") (pintype "input+no_connect"))
    )
    (net (code "149") (name "unconnected-(U9-P1.7-Pad6)") (class "Default")
      (node (ref "U9") (pin "6") (pinfunction "P1.7_6") (pintype "input+no_connect"))
    )
    (net (code "150") (name "unconnected-(U9-P2.0-Pad5)") (class "Default")
      (node (ref "U9") (pin "5") (pinfunction "P2.0_5") (pintype "input+no_connect"))
    )
    (net (code "151") (name "unconnected-(U9-P2.1-Pad4)") (class "Default")
      (node (ref "U9") (pin "4") (pinfunction "P2.1_4") (pintype "input+no_connect"))
    )
    (net (code "152") (name "unconnected-(U9-P2.2-Pad3)") (class "Default")
      (node (ref "U9") (pin "3") (pinfunction "P2.2_3") (pintype "input+no_connect"))
    )
    (net (code "153") (name "unconnected-(U11-Pad3)") (class "Default")
      (node (ref "U11") (pin "3") (pinfunction "3_3") (pintype "unspecified+no_connect"))
    )
    (net (code "154") (name "unconnected-(U11-Pad4)") (class "Default")
      (node (ref "U11") (pin "4") (pinfunction "4_4") (pintype "unspecified+no_connect"))
    )
    (net (code "155") (name "unconnected-(U13-INPUT1-Pad8)") (class "Default")
      (node (ref "U13") (pin "8") (pinfunction "INPUT1_8") (pintype "unspecified+no_connect"))
    )
    (net (code "156") (name "unconnected-(U13-INPUT2-Pad10)") (class "Default")
      (node (ref "U13") (pin "10") (pinfunction "INPUT2_10") (pintype "unspecified+no_connect"))
    )
    (net (code "157") (name "unconnected-(U13-INPUT3-Pad7)") (class "Default")
      (node (ref "U13") (pin "7") (pinfunction "INPUT3_7") (pintype "unspecified+no_connect"))
    )
    (net (code "158") (name "unconnected-(U13-INPUT4-Pad12)") (class "Default")
      (node (ref "U13") (pin "12") (pinfunction "INPUT4_12") (pintype "unspecified+no_connect"))
    )
    (net (code "159") (name "unconnected-(U13-INPUT5-Pad5)") (class "Default")
      (node (ref "U13") (pin "5") (pinfunction "INPUT5_5") (pintype "unspecified+no_connect"))
    )
    (net (code "160") (name "unconnected-(U13-NC-Pad2)") (class "Default")
      (node (ref "U13") (pin "2") (pinfunction "NC_2") (pintype "unspecified+no_connect"))
    )
    (net (code "161") (name "unconnected-(U13-NC-Pad3)") (class "Default")
      (node (ref "U13") (pin "3") (pinfunction "NC_3") (pintype "unspecified+no_connect"))
    )
    (net (code "162") (name "unconnected-(U13-NC-Pad4)") (class "Default")
      (node (ref "U13") (pin "4") (pinfunction "NC_4") (pintype "unspecified+no_connect"))
    )
    (net (code "163") (name "unconnected-(U13-NC-Pad9)") (class "Default")
      (node (ref "U13") (pin "9") (pinfunction "NC_9") (pintype "unspecified+no_connect"))
    )
    (net (code "164") (name "unconnected-(U13-NC-Pad14)") (class "Default")
      (node (ref "U13") (pin "14") (pinfunction "NC_14") (pintype "unspecified+no_connect"))
    )
    (net (code "165") (name "unconnected-(U13-NC-Pad15)") (class "Default")
      (node (ref "U13") (pin "15") (pinfunction "NC_15") (pintype "unspecified+no_connect"))
    )
    (net (code "166") (name "unconnected-(U13-OUT1-Pad16)") (class "Default")
      (node (ref "U13") (pin "16") (pinfunction "OUT1_16") (pintype "unspecified+no_connect"))
    )
    (net (code "167") (name "unconnected-(U13-OUT2-Pad11)") (class "Default")
      (node (ref "U13") (pin "11") (pinfunction "OUT2_11") (pintype "unspecified+no_connect"))
    )
    (net (code "168") (name "unconnected-(U13-OUT3-Pad18)") (class "Default")
      (node (ref "U13") (pin "18") (pinfunction "OUT3_18") (pintype "unspecified+no_connect"))
    )
    (net (code "169") (name "unconnected-(U13-OUT4-Pad21)") (class "Default")
      (node (ref "U13") (pin "21") (pinfunction "OUT4_21") (pintype "unspecified+no_connect"))
    )
    (net (code "170") (name "unconnected-(U13-OUT5-Pad13)") (class "Default")
      (node (ref "U13") (pin "13") (pinfunction "OUT5_13") (pintype "unspecified+no_connect"))
    )
    (net (code "171") (name "unconnected-(U14-BAT-Pad1)") (class "Default")
      (node (ref "U14") (pin "1") (pinfunction "BAT_1") (pintype "input+no_connect"))
    )
    (net (code "172") (name "unconnected-(U14-BOOT-Pad12)") (class "Default")
      (node (ref "U14") (pin "12") (pinfunction "BOOT_12") (pintype "input+no_connect"))
    )
    (net (code "173") (name "unconnected-(U14-DN-Pad10)") (class "Default")
      (node (ref "U14") (pin "10") (pinfunction "DN_10") (pintype "input+no_connect"))
    )
    (net (code "174") (name "unconnected-(U14-DP-Pad9)") (class "Default")
      (node (ref "U14") (pin "9") (pinfunction "DP_9") (pintype "input+no_connect"))
    )
    (net (code "175") (name "unconnected-(U14-EN-Pad2)") (class "Default")
      (node (ref "U14") (pin "2") (pinfunction "EN_2") (pintype "input+no_connect"))
    )
    (net (code "176") (name "unconnected-(U14-GND-Pad8)") (class "Default")
      (node (ref "U14") (pin "8") (pinfunction "GND_8") (pintype "input+no_connect"))
    )
    (net (code "177") (name "unconnected-(U14-LED-Pad11)") (class "Default")
      (node (ref "U14") (pin "11") (pinfunction "LED_11") (pintype "input+no_connect"))
    )
    (net (code "178") (name "unconnected-(U14-VCC-Pad7)") (class "Default")
      (node (ref "U14") (pin "7") (pinfunction "VCC_7") (pintype "input+no_connect"))
    )
    (net (code "179") (name "unconnected-(USBC1-Pad0)") (class "Default")
      (node (ref "USBC1") (pin "0") (pinfunction "0_0") (pintype "input+no_connect"))
    )
    (net (code "180") (name "unconnected-(USBC1-Pad1)") (class "Default")
      (node (ref "USBC1") (pin "1") (pinfunction "1_1") (pintype "input+no_connect"))
    )
    (net (code "181") (name "unconnected-(USBC1-Pad2)") (class "Default")
      (node (ref "USBC1") (pin "2") (pinfunction "2_2") (pintype "input+no_connect"))
    )
    (net (code "182") (name "unconnected-(USBC1-Pad3)") (class "Default")
      (node (ref "USBC1") (pin "3") (pinfunction "3_3") (pintype "input+no_connect"))
    )
    (net (code "183") (name "unconnected-(USBC1-SBU1-PadA8)") (class "Default")
      (node (ref "USBC1") (pin "A8") (pinfunction "SBU1_A8") (pintype "input+no_connect"))
    )
    (net (code "184") (name "unconnected-(USBC1-SBU2-PadB8)") (class "Default")
      (node (ref "USBC1") (pin "B8") (pinfunction "SBU2_B8") (pintype "input+no_connect"))
    )
  )
)
